# axiom_beta_sensor_cmv12000_tht_v0_16_r1_.net
KiCad netlist of a schematic drawn in EAGLE
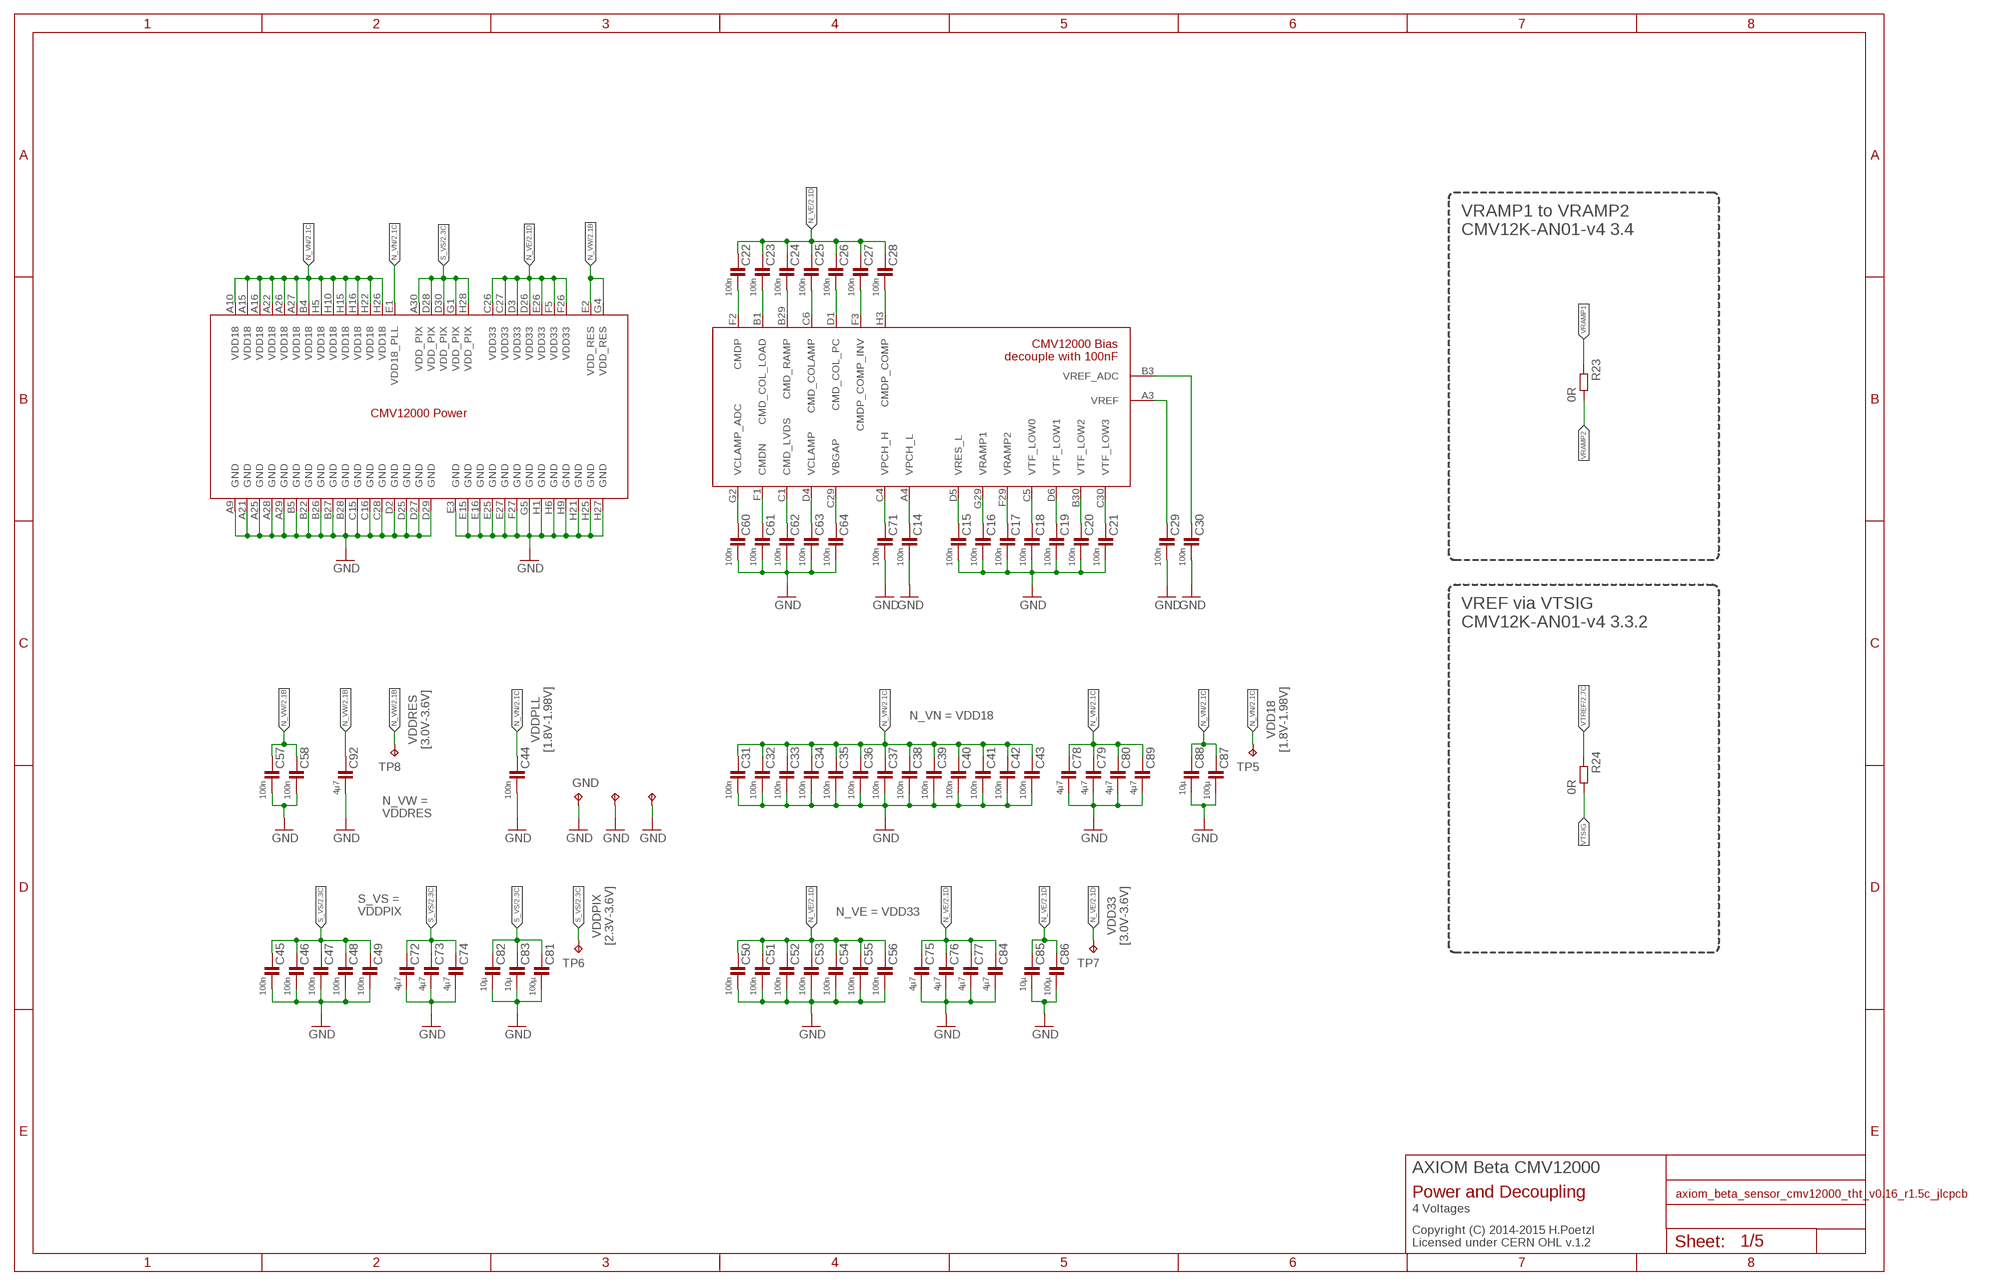
[diagram p0: schematic, sheet 1]
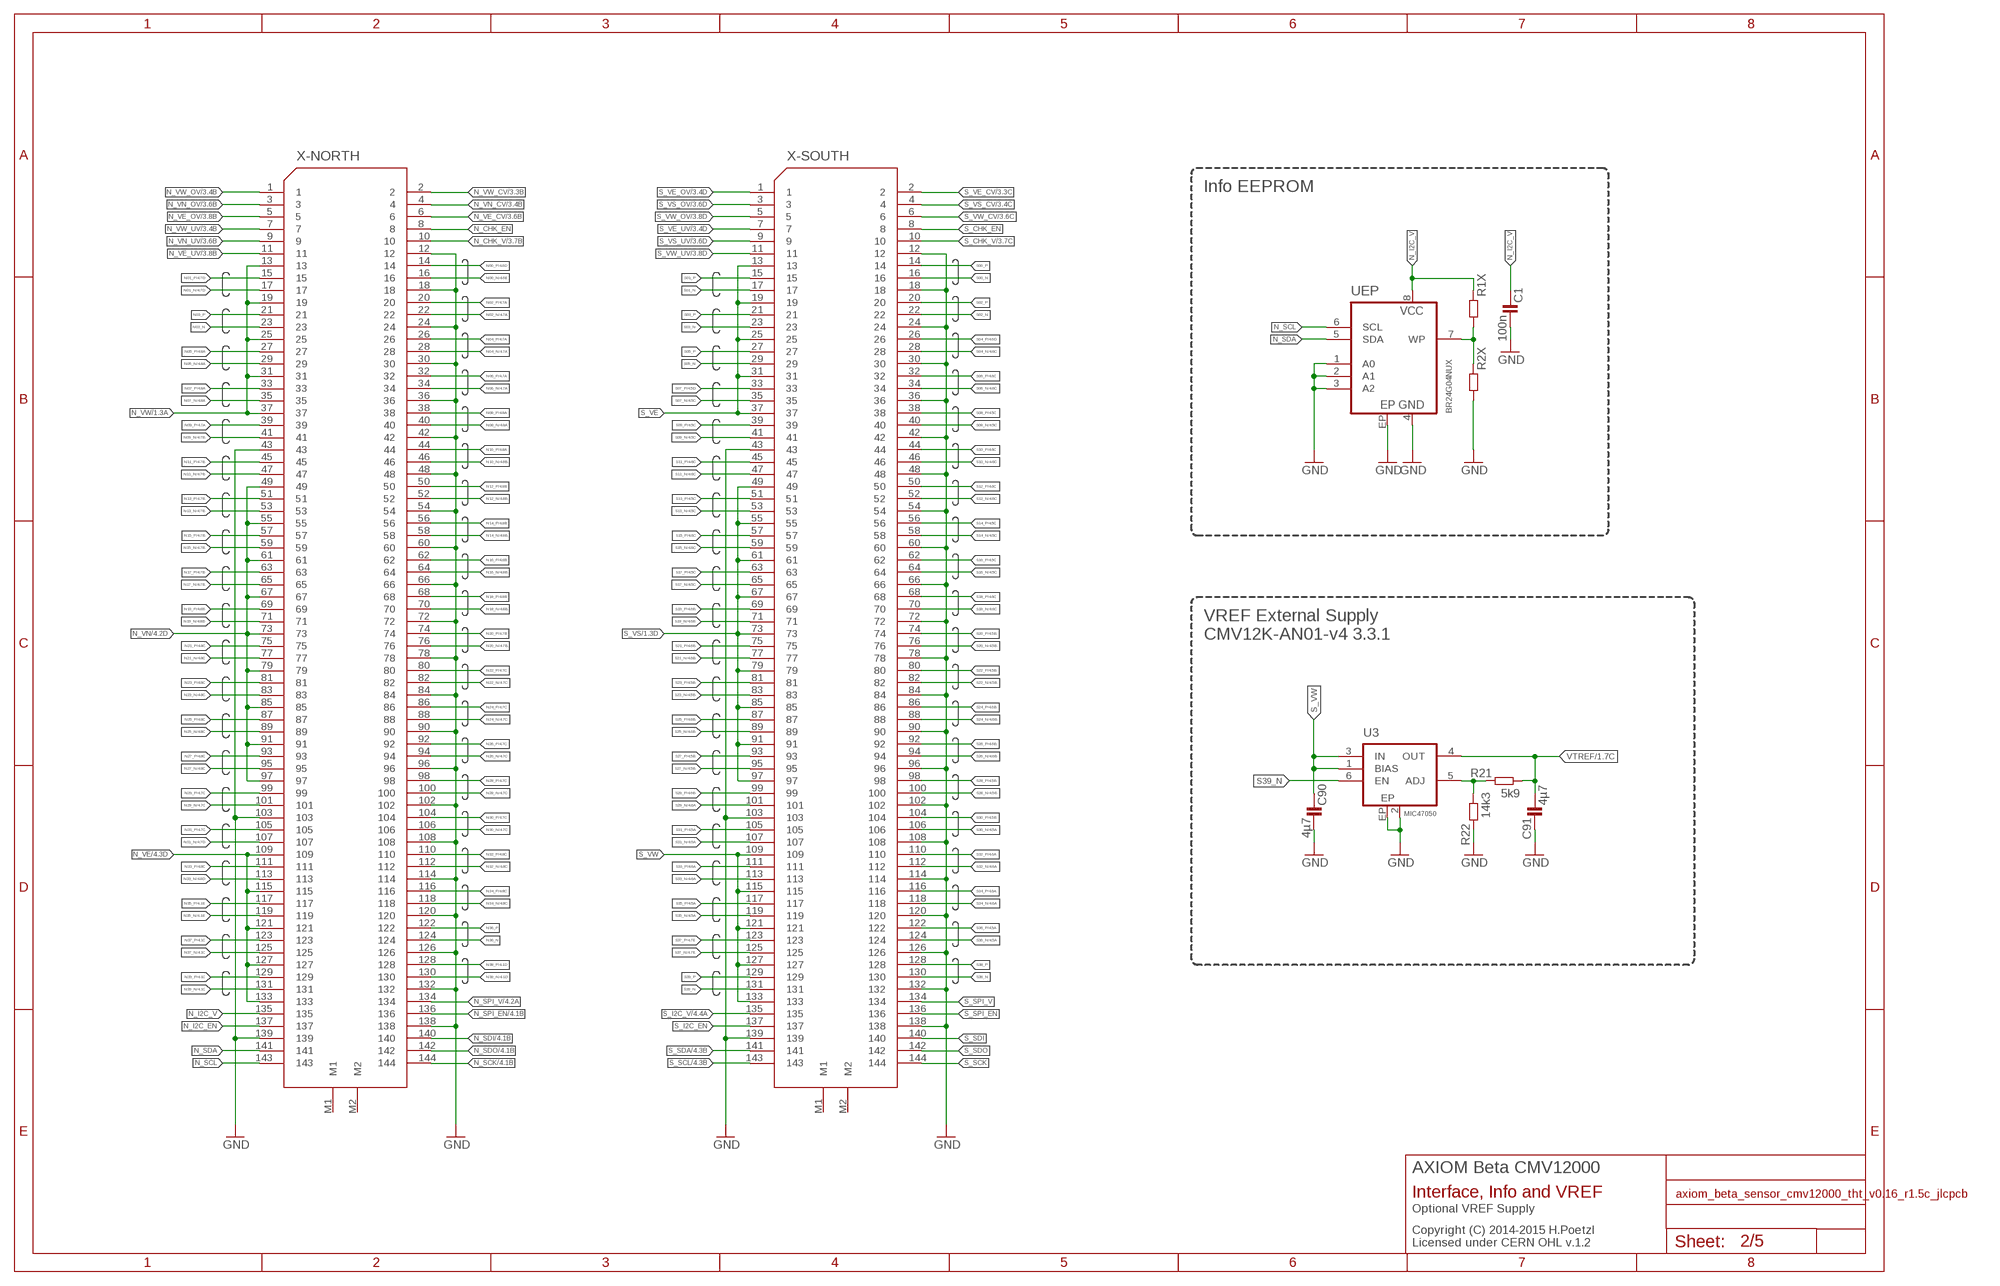
[diagram p1: schematic, sheet 2]
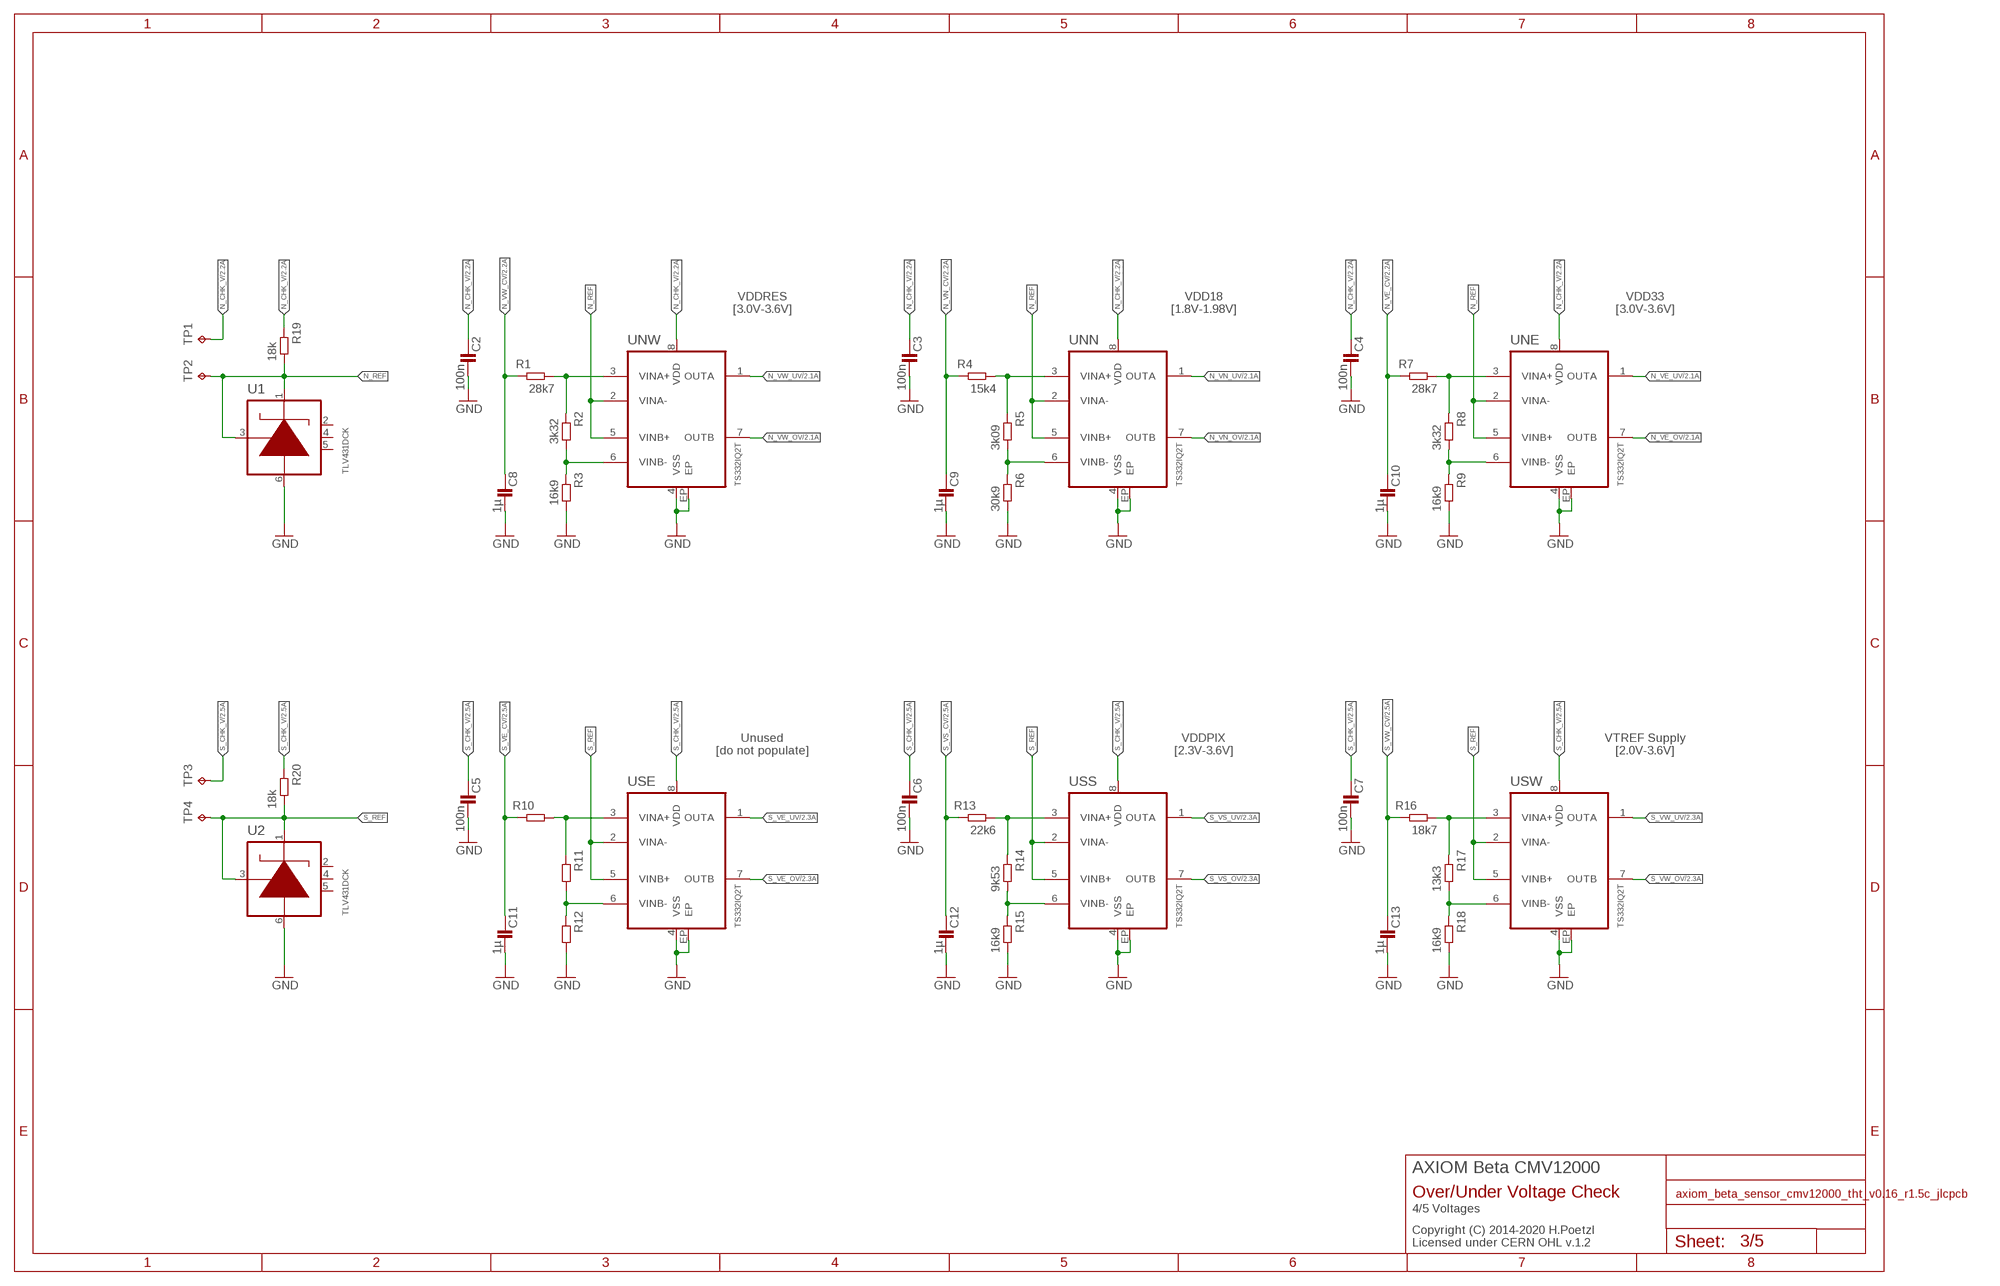
[diagram p2: schematic, sheet 3]
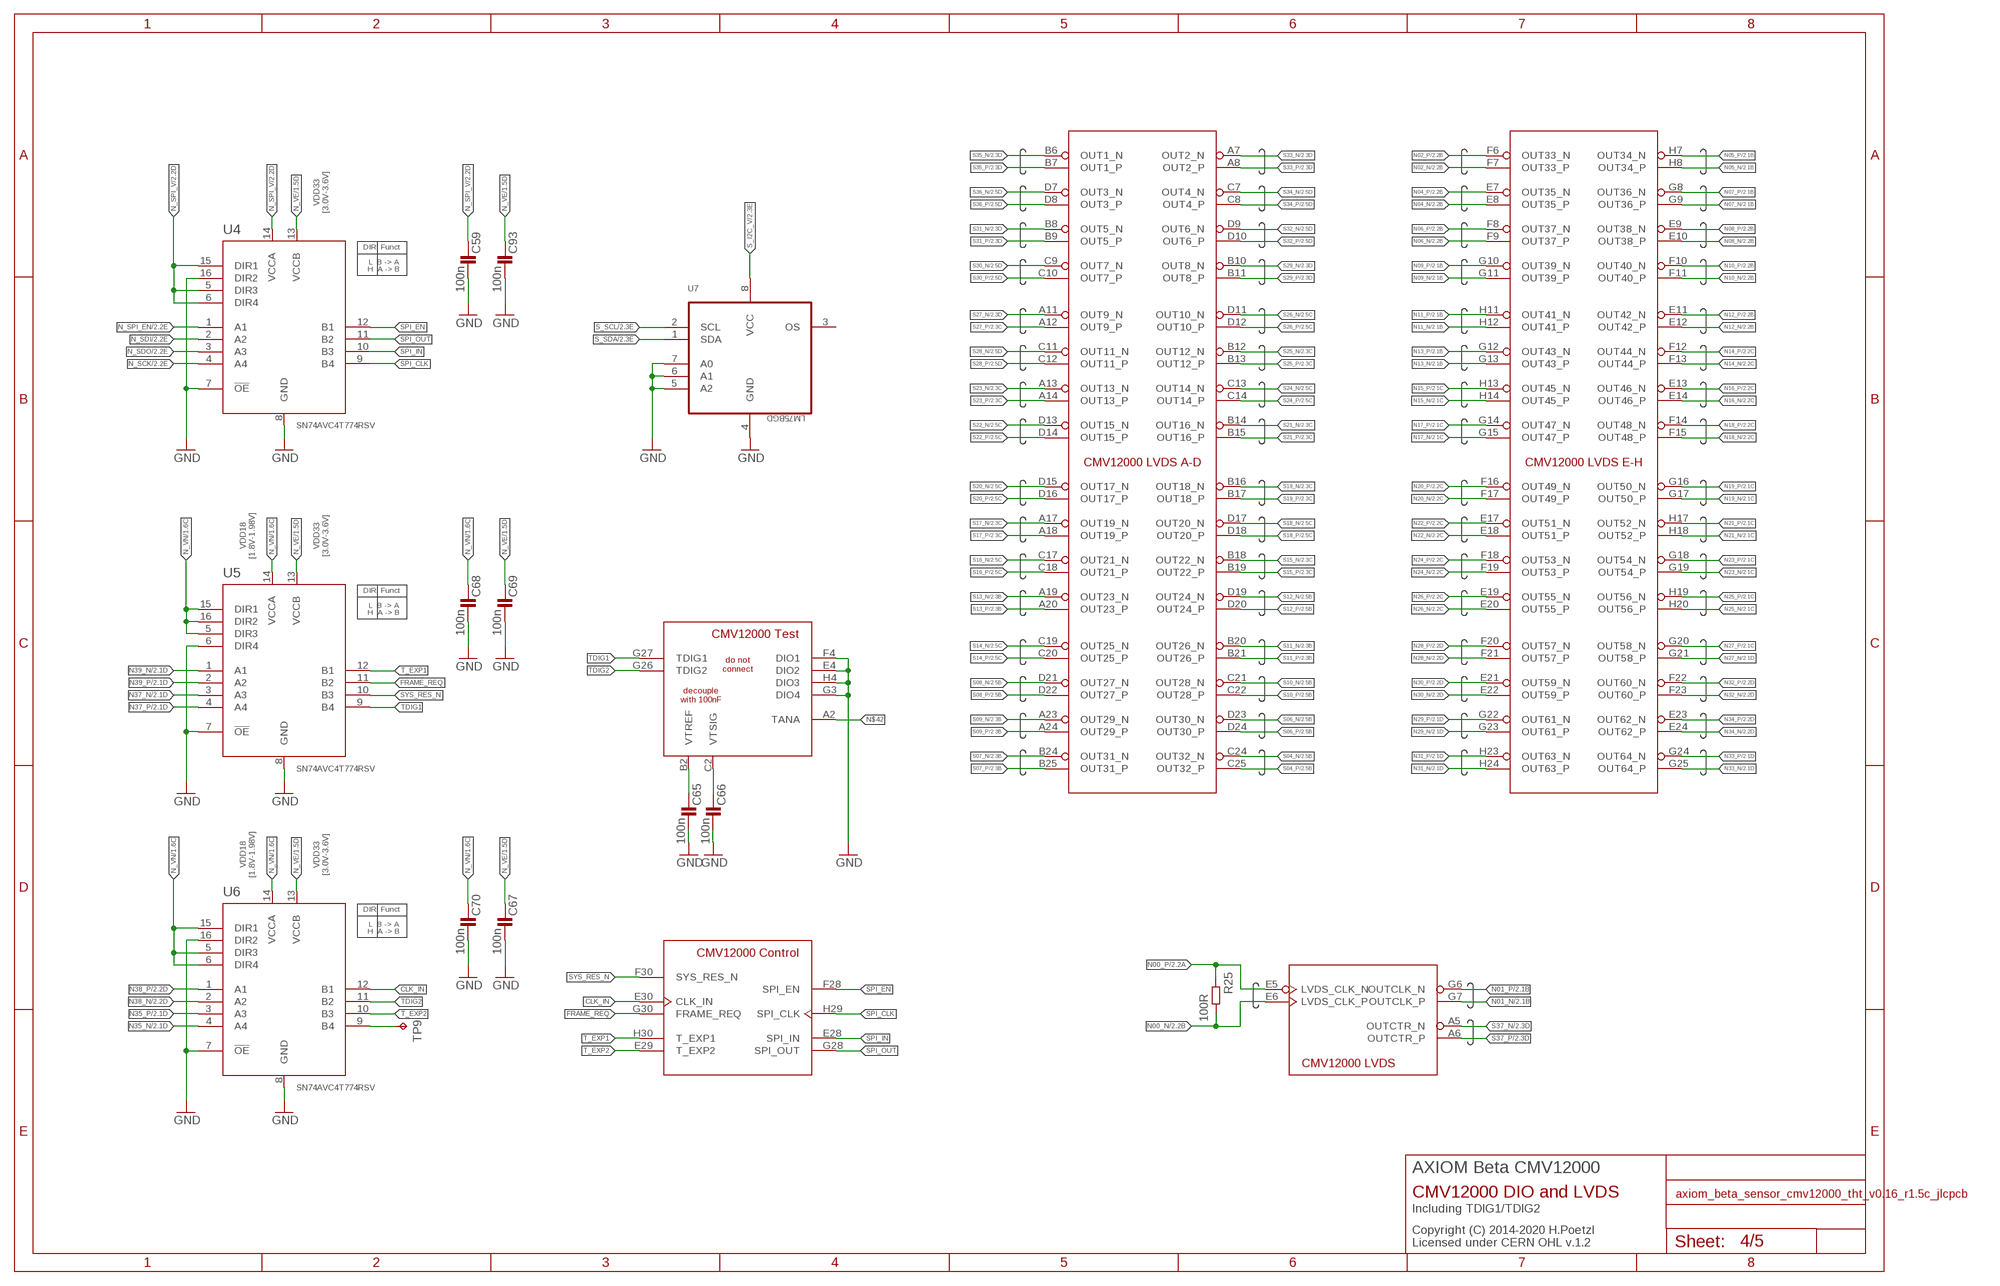
[diagram p3: schematic, sheet 4]
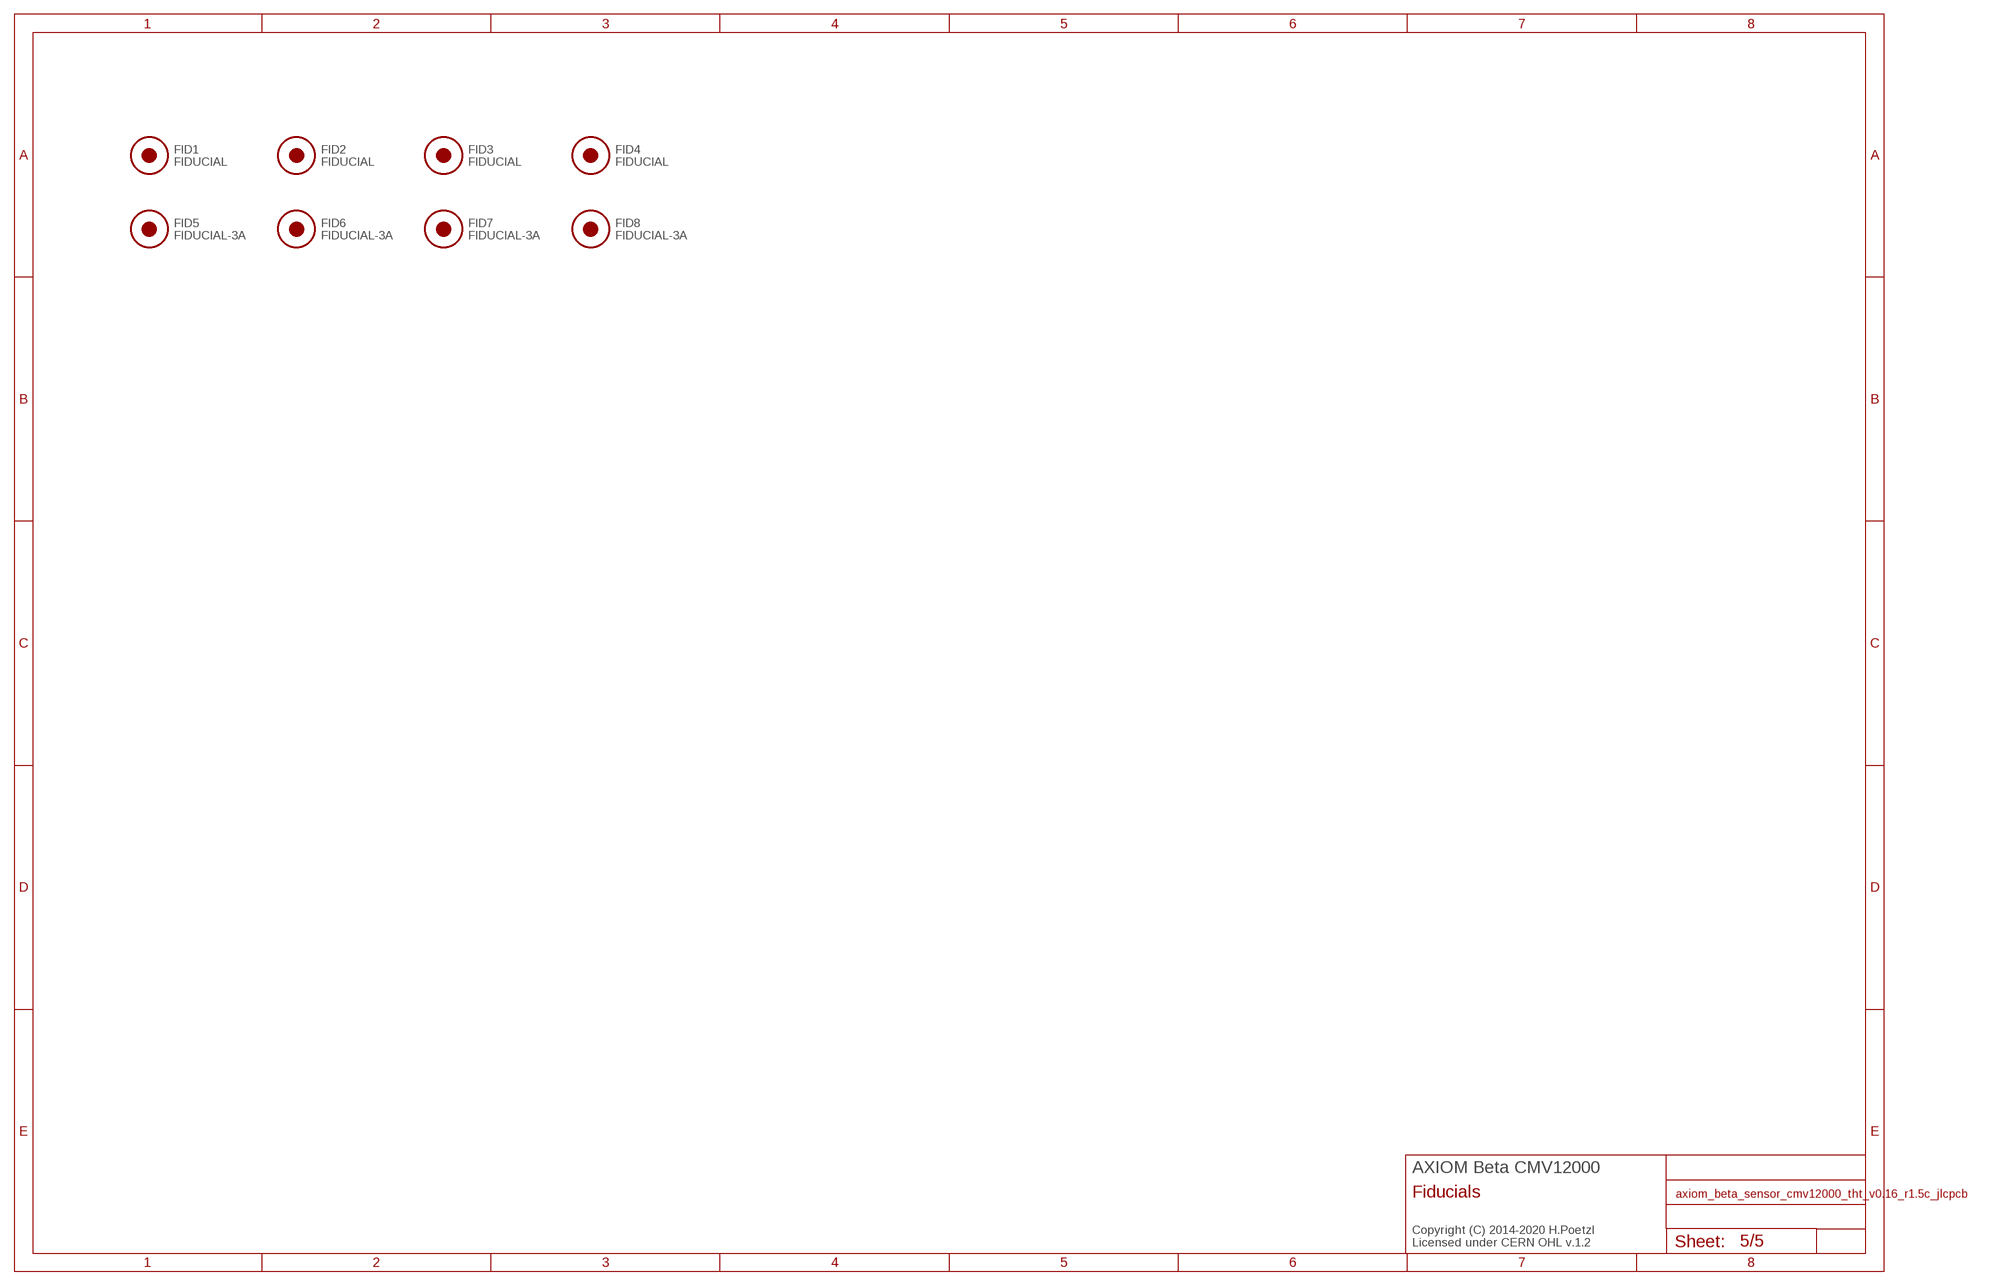
[diagram p4: schematic, sheet 5]

(export (version "E")
  (design (tool "Eeschema 10.0.6"))
  (components
    (comp (ref "C1")
      (value "100n")
      (footprint "eagle-import:0402-C")
      (libsource (lib "eagle-import") (part "C0402-C"))
    )
    (comp (ref "C90")
      (value "4µ7")
      (footprint "eagle-import:0402-C")
      (libsource (lib "eagle-import") (part "C0402-C"))
    )
    (comp (ref "C91")
      (value "4µ7")
      (footprint "eagle-import:0402-C")
      (libsource (lib "eagle-import") (part "C0402-C"))
    )
    (comp (ref "R1X")
      (value "R0402-C")
      (footprint "eagle-import:0402-C")
      (libsource (lib "eagle-import") (part "R0402-C"))
    )
    (comp (ref "R2X")
      (value "R0402-C")
      (footprint "eagle-import:0402-C")
      (libsource (lib "eagle-import") (part "R0402-C"))
    )
    (comp (ref "R21")
      (value "5k9")
      (footprint "eagle-import:0402-C")
      (libsource (lib "eagle-import") (part "R0402-C"))
    )
    (comp (ref "R22")
      (value "14k3")
      (footprint "eagle-import:0402-C")
      (libsource (lib "eagle-import") (part "R0402-C"))
    )
    (comp (ref "U3")
      (value "MIC47050")
      (footprint "eagle-import:MLF-6")
      (libsource (lib "eagle-import") (part "MIC47050-ADJ"))
    )
    (comp (ref "UEP")
      (value "BR24G04NUX")
      (footprint "eagle-import:DFN200X300X100-9N")
      (libsource (lib "eagle-import") (part "BR24G04NUX"))
    )
    (comp (ref "X-NORTH")
      (value "FX10-144P")
      (footprint "eagle-import:FX10A-144P")
      (libsource (lib "eagle-import") (part "FX10-144P"))
    )
    (comp (ref "X-SOUTH")
      (value "FX10-144P")
      (footprint "eagle-import:FX10A-144P")
      (libsource (lib "eagle-import") (part "FX10-144P"))
    )
    (comp (ref "FID1")
      (value "FIDUCIAL")
      (footprint "eagle-import:FID_ARROW")
      (libsource (lib "eagle-import") (part "FIDUCIAL"))
    )
    (comp (ref "FID2")
      (value "FIDUCIAL")
      (footprint "eagle-import:FID_ARROW")
      (libsource (lib "eagle-import") (part "FIDUCIAL"))
    )
    (comp (ref "FID3")
      (value "FIDUCIAL")
      (footprint "eagle-import:FID_ARROW")
      (libsource (lib "eagle-import") (part "FIDUCIAL"))
    )
    (comp (ref "FID4")
      (value "FIDUCIAL")
      (footprint "eagle-import:FID_ARROW")
      (libsource (lib "eagle-import") (part "FIDUCIAL"))
    )
    (comp (ref "FID5")
      (value "FIDUCIAL-3A")
      (footprint "eagle-import:FID_3ARROW")
      (libsource (lib "eagle-import") (part "FIDUCIAL-3A"))
    )
    (comp (ref "FID6")
      (value "FIDUCIAL-3A")
      (footprint "eagle-import:FID_3ARROW")
      (libsource (lib "eagle-import") (part "FIDUCIAL-3A"))
    )
    (comp (ref "FID7")
      (value "FIDUCIAL-3A")
      (footprint "eagle-import:FID_3ARROW")
      (libsource (lib "eagle-import") (part "FIDUCIAL-3A"))
    )
    (comp (ref "FID8")
      (value "FIDUCIAL-3A")
      (footprint "eagle-import:FID_3ARROW")
      (libsource (lib "eagle-import") (part "FIDUCIAL-3A"))
    )
    (comp (ref "C59")
      (value "100n")
      (footprint "eagle-import:0402-C")
      (libsource (lib "eagle-import") (part "C0402-C"))
    )
    (comp (ref "C65")
      (value "100n")
      (footprint "eagle-import:0402-C")
      (libsource (lib "eagle-import") (part "C0402-C"))
    )
    (comp (ref "C66")
      (value "100n")
      (footprint "eagle-import:0402-C")
      (libsource (lib "eagle-import") (part "C0402-C"))
    )
    (comp (ref "C67")
      (value "100n")
      (footprint "eagle-import:0402-C")
      (libsource (lib "eagle-import") (part "C0402-C"))
    )
    (comp (ref "C68")
      (value "100n")
      (footprint "eagle-import:0402-C")
      (libsource (lib "eagle-import") (part "C0402-C"))
    )
    (comp (ref "C69")
      (value "100n")
      (footprint "eagle-import:0402-C")
      (libsource (lib "eagle-import") (part "C0402-C"))
    )
    (comp (ref "C70")
      (value "100n")
      (footprint "eagle-import:0402-C")
      (libsource (lib "eagle-import") (part "C0402-C"))
    )
    (comp (ref "C93")
      (value "100n")
      (footprint "eagle-import:0402-C")
      (libsource (lib "eagle-import") (part "C0402-C"))
    )
    (comp (ref "R25")
      (value "100R")
      (footprint "eagle-import:0402-C")
      (libsource (lib "eagle-import") (part "R0402-C"))
    )
    (comp (ref "SENSOR")
      (value "CMV12000JLCPCB")
      (footprint "eagle-import:10-30-07-237-400T4-JLCPCB")
      (libsource (lib "eagle-import") (part "CMV12000JLCPCB"))
    )
    (comp (ref "TP9")
      (value "TPTP10R")
      (footprint "eagle-import:TP10R")
      (libsource (lib "eagle-import") (part "TPTP10R"))
    )
    (comp (ref "U4")
      (value "SN74AVC4T774RSV")
      (footprint "eagle-import:QFN40P185X265X55-16N")
      (libsource (lib "eagle-import") (part "SN74AVC4T774RSV"))
    )
    (comp (ref "U5")
      (value "SN74AVC4T774RSV")
      (footprint "eagle-import:QFN40P185X265X55-16N")
      (libsource (lib "eagle-import") (part "SN74AVC4T774RSV"))
    )
    (comp (ref "U6")
      (value "SN74AVC4T774RSV")
      (footprint "eagle-import:QFN40P185X265X55-16N")
      (libsource (lib "eagle-import") (part "SN74AVC4T774RSV"))
    )
    (comp (ref "U7")
      (value "LM75BGD")
      (footprint "eagle-import:SOT996-2_3")
      (libsource (lib "eagle-import") (part "LM75BGD"))
    )
    (comp (ref "C2")
      (value "100n")
      (footprint "eagle-import:0402-C")
      (libsource (lib "eagle-import") (part "C0402-C"))
    )
    (comp (ref "C3")
      (value "100n")
      (footprint "eagle-import:0402-C")
      (libsource (lib "eagle-import") (part "C0402-C"))
    )
    (comp (ref "C4")
      (value "100n")
      (footprint "eagle-import:0402-C")
      (libsource (lib "eagle-import") (part "C0402-C"))
    )
    (comp (ref "C5")
      (value "100n")
      (footprint "eagle-import:0402-C")
      (libsource (lib "eagle-import") (part "C0402-C"))
    )
    (comp (ref "C6")
      (value "100n")
      (footprint "eagle-import:0402-C")
      (libsource (lib "eagle-import") (part "C0402-C"))
    )
    (comp (ref "C7")
      (value "100n")
      (footprint "eagle-import:0402-C")
      (libsource (lib "eagle-import") (part "C0402-C"))
    )
    (comp (ref "C8")
      (value "1µ")
      (footprint "eagle-import:0402-C")
      (libsource (lib "eagle-import") (part "C0402-C"))
    )
    (comp (ref "C9")
      (value "1µ")
      (footprint "eagle-import:0402-C")
      (libsource (lib "eagle-import") (part "C0402-C"))
    )
    (comp (ref "C10")
      (value "1µ")
      (footprint "eagle-import:0402-C")
      (libsource (lib "eagle-import") (part "C0402-C"))
    )
    (comp (ref "C11")
      (value "1µ")
      (footprint "eagle-import:0402-C")
      (libsource (lib "eagle-import") (part "C0402-C"))
    )
    (comp (ref "C12")
      (value "1µ")
      (footprint "eagle-import:0402-C")
      (libsource (lib "eagle-import") (part "C0402-C"))
    )
    (comp (ref "C13")
      (value "1µ")
      (footprint "eagle-import:0402-C")
      (libsource (lib "eagle-import") (part "C0402-C"))
    )
    (comp (ref "R1")
      (value "28k7")
      (footprint "eagle-import:0402-C")
      (libsource (lib "eagle-import") (part "R0402-C"))
    )
    (comp (ref "R2")
      (value "3k32")
      (footprint "eagle-import:0402-C")
      (libsource (lib "eagle-import") (part "R0402-C"))
    )
    (comp (ref "R3")
      (value "16k9")
      (footprint "eagle-import:0402-C")
      (libsource (lib "eagle-import") (part "R0402-C"))
    )
    (comp (ref "R4")
      (value "15k4")
      (footprint "eagle-import:0402-C")
      (libsource (lib "eagle-import") (part "R0402-C"))
    )
    (comp (ref "R5")
      (value "3k09")
      (footprint "eagle-import:0402-C")
      (libsource (lib "eagle-import") (part "R0402-C"))
    )
    (comp (ref "R6")
      (value "30k9")
      (footprint "eagle-import:0402-C")
      (libsource (lib "eagle-import") (part "R0402-C"))
    )
    (comp (ref "R7")
      (value "28k7")
      (footprint "eagle-import:0402-C")
      (libsource (lib "eagle-import") (part "R0402-C"))
    )
    (comp (ref "R8")
      (value "3k32")
      (footprint "eagle-import:0402-C")
      (libsource (lib "eagle-import") (part "R0402-C"))
    )
    (comp (ref "R9")
      (value "16k9")
      (footprint "eagle-import:0402-C")
      (libsource (lib "eagle-import") (part "R0402-C"))
    )
    (comp (ref "R10")
      (value "R0402-C")
      (footprint "eagle-import:0402-C")
      (libsource (lib "eagle-import") (part "R0402-C"))
    )
    (comp (ref "R11")
      (value "R0402-C")
      (footprint "eagle-import:0402-C")
      (libsource (lib "eagle-import") (part "R0402-C"))
    )
    (comp (ref "R12")
      (value "R0402-C")
      (footprint "eagle-import:0402-C")
      (libsource (lib "eagle-import") (part "R0402-C"))
    )
    (comp (ref "R13")
      (value "22k6")
      (footprint "eagle-import:0402-C")
      (libsource (lib "eagle-import") (part "R0402-C"))
    )
    (comp (ref "R14")
      (value "9k53")
      (footprint "eagle-import:0402-C")
      (libsource (lib "eagle-import") (part "R0402-C"))
    )
    (comp (ref "R15")
      (value "16k9")
      (footprint "eagle-import:0402-C")
      (libsource (lib "eagle-import") (part "R0402-C"))
    )
    (comp (ref "R16")
      (value "18k7")
      (footprint "eagle-import:0402-C")
      (libsource (lib "eagle-import") (part "R0402-C"))
    )
    (comp (ref "R17")
      (value "13k3")
      (footprint "eagle-import:0402-C")
      (libsource (lib "eagle-import") (part "R0402-C"))
    )
    (comp (ref "R18")
      (value "16k9")
      (footprint "eagle-import:0402-C")
      (libsource (lib "eagle-import") (part "R0402-C"))
    )
    (comp (ref "R19")
      (value "18k")
      (footprint "eagle-import:0402-C")
      (libsource (lib "eagle-import") (part "R0402-C"))
    )
    (comp (ref "R20")
      (value "18k")
      (footprint "eagle-import:0402-C")
      (libsource (lib "eagle-import") (part "R0402-C"))
    )
    (comp (ref "TP1")
      (value "TPTP10R")
      (footprint "eagle-import:TP10R")
      (libsource (lib "eagle-import") (part "TPTP10R"))
    )
    (comp (ref "TP2")
      (value "TPTP10R")
      (footprint "eagle-import:TP10R")
      (libsource (lib "eagle-import") (part "TPTP10R"))
    )
    (comp (ref "TP3")
      (value "TPTP10R")
      (footprint "eagle-import:TP10R")
      (libsource (lib "eagle-import") (part "TPTP10R"))
    )
    (comp (ref "TP4")
      (value "TPTP10R")
      (footprint "eagle-import:TP10R")
      (libsource (lib "eagle-import") (part "TPTP10R"))
    )
    (comp (ref "U1")
      (value "TLV431DCK")
      (footprint "eagle-import:SOT65P210X110-6N")
      (libsource (lib "eagle-import") (part "TLV431DCK"))
    )
    (comp (ref "U2")
      (value "TLV431DCK")
      (footprint "eagle-import:SOT65P210X110-6N")
      (libsource (lib "eagle-import") (part "TLV431DCK"))
    )
    (comp (ref "UNE")
      (value "TS332IQ2T")
      (footprint "eagle-import:DFN200X200X100-9N")
      (libsource (lib "eagle-import") (part "TS332IQ2T"))
    )
    (comp (ref "UNN")
      (value "TS332IQ2T")
      (footprint "eagle-import:DFN200X200X100-9N")
      (libsource (lib "eagle-import") (part "TS332IQ2T"))
    )
    (comp (ref "UNW")
      (value "TS332IQ2T")
      (footprint "eagle-import:DFN200X200X100-9N")
      (libsource (lib "eagle-import") (part "TS332IQ2T"))
    )
    (comp (ref "USE")
      (value "TS332IQ2T")
      (footprint "eagle-import:DFN200X200X100-9N")
      (libsource (lib "eagle-import") (part "TS332IQ2T"))
    )
    (comp (ref "USS")
      (value "TS332IQ2T")
      (footprint "eagle-import:DFN200X200X100-9N")
      (libsource (lib "eagle-import") (part "TS332IQ2T"))
    )
    (comp (ref "USW")
      (value "TS332IQ2T")
      (footprint "eagle-import:DFN200X200X100-9N")
      (libsource (lib "eagle-import") (part "TS332IQ2T"))
    )
    (comp (ref "C14")
      (value "100n")
      (footprint "eagle-import:0402-C")
      (libsource (lib "eagle-import") (part "C0402-C"))
    )
    (comp (ref "C15")
      (value "100n")
      (footprint "eagle-import:0402-C")
      (libsource (lib "eagle-import") (part "C0402-C"))
    )
    (comp (ref "C16")
      (value "100n")
      (footprint "eagle-import:0402-C")
      (libsource (lib "eagle-import") (part "C0402-C"))
    )
    (comp (ref "C17")
      (value "100n")
      (footprint "eagle-import:0402-C")
      (libsource (lib "eagle-import") (part "C0402-C"))
    )
    (comp (ref "C18")
      (value "100n")
      (footprint "eagle-import:0402-C")
      (libsource (lib "eagle-import") (part "C0402-C"))
    )
    (comp (ref "C19")
      (value "100n")
      (footprint "eagle-import:0402-C")
      (libsource (lib "eagle-import") (part "C0402-C"))
    )
    (comp (ref "C20")
      (value "100n")
      (footprint "eagle-import:0402-C")
      (libsource (lib "eagle-import") (part "C0402-C"))
    )
    (comp (ref "C21")
      (value "100n")
      (footprint "eagle-import:0402-C")
      (libsource (lib "eagle-import") (part "C0402-C"))
    )
    (comp (ref "C22")
      (value "100n")
      (footprint "eagle-import:0402-C")
      (libsource (lib "eagle-import") (part "C0402-C"))
    )
    (comp (ref "C23")
      (value "100n")
      (footprint "eagle-import:0402-C")
      (libsource (lib "eagle-import") (part "C0402-C"))
    )
    (comp (ref "C24")
      (value "100n")
      (footprint "eagle-import:0402-C")
      (libsource (lib "eagle-import") (part "C0402-C"))
    )
    (comp (ref "C25")
      (value "100n")
      (footprint "eagle-import:0402-C")
      (libsource (lib "eagle-import") (part "C0402-C"))
    )
    (comp (ref "C26")
      (value "100n")
      (footprint "eagle-import:0402-C")
      (libsource (lib "eagle-import") (part "C0402-C"))
    )
    (comp (ref "C27")
      (value "100n")
      (footprint "eagle-import:0402-C")
      (libsource (lib "eagle-import") (part "C0402-C"))
    )
    (comp (ref "C28")
      (value "100n")
      (footprint "eagle-import:0402-C")
      (libsource (lib "eagle-import") (part "C0402-C"))
    )
    (comp (ref "C29")
      (value "100n")
      (footprint "eagle-import:0402-C")
      (libsource (lib "eagle-import") (part "C0402-C"))
    )
    (comp (ref "C30")
      (value "100n")
      (footprint "eagle-import:0402-C")
      (libsource (lib "eagle-import") (part "C0402-C"))
    )
    (comp (ref "C31")
      (value "100n")
      (footprint "eagle-import:0402-C")
      (libsource (lib "eagle-import") (part "C0402-C"))
    )
    (comp (ref "C32")
      (value "100n")
      (footprint "eagle-import:0402-C")
      (libsource (lib "eagle-import") (part "C0402-C"))
    )
    (comp (ref "C33")
      (value "100n")
      (footprint "eagle-import:0402-C")
      (libsource (lib "eagle-import") (part "C0402-C"))
    )
    (comp (ref "C34")
      (value "100n")
      (footprint "eagle-import:0402-C")
      (libsource (lib "eagle-import") (part "C0402-C"))
    )
    (comp (ref "C35")
      (value "100n")
      (footprint "eagle-import:0402-C")
      (libsource (lib "eagle-import") (part "C0402-C"))
    )
    (comp (ref "C36")
      (value "100n")
      (footprint "eagle-import:0402-C")
      (libsource (lib "eagle-import") (part "C0402-C"))
    )
    (comp (ref "C37")
      (value "100n")
      (footprint "eagle-import:0402-C")
      (libsource (lib "eagle-import") (part "C0402-C"))
    )
    (comp (ref "C38")
      (value "100n")
      (footprint "eagle-import:0402-C")
      (libsource (lib "eagle-import") (part "C0402-C"))
    )
    (comp (ref "C39")
      (value "100n")
      (footprint "eagle-import:0402-C")
      (libsource (lib "eagle-import") (part "C0402-C"))
    )
    (comp (ref "C40")
      (value "100n")
      (footprint "eagle-import:0402-C")
      (libsource (lib "eagle-import") (part "C0402-C"))
    )
    (comp (ref "C41")
      (value "100n")
      (footprint "eagle-import:0402-C")
      (libsource (lib "eagle-import") (part "C0402-C"))
    )
    (comp (ref "C42")
      (value "100n")
      (footprint "eagle-import:0402-C")
      (libsource (lib "eagle-import") (part "C0402-C"))
    )
    (comp (ref "C43")
      (value "100n")
      (footprint "eagle-import:0402-C")
      (libsource (lib "eagle-import") (part "C0402-C"))
    )
    (comp (ref "C44")
      (value "100n")
      (footprint "eagle-import:0402-C")
      (libsource (lib "eagle-import") (part "C0402-C"))
    )
    (comp (ref "C45")
      (value "100n")
      (footprint "eagle-import:0402-C")
      (libsource (lib "eagle-import") (part "C0402-C"))
    )
    (comp (ref "C46")
      (value "100n")
      (footprint "eagle-import:0402-C")
      (libsource (lib "eagle-import") (part "C0402-C"))
    )
    (comp (ref "C47")
      (value "100n")
      (footprint "eagle-import:0402-C")
      (libsource (lib "eagle-import") (part "C0402-C"))
    )
    (comp (ref "C48")
      (value "100n")
      (footprint "eagle-import:0402-C")
      (libsource (lib "eagle-import") (part "C0402-C"))
    )
    (comp (ref "C49")
      (value "100n")
      (footprint "eagle-import:0402-C")
      (libsource (lib "eagle-import") (part "C0402-C"))
    )
    (comp (ref "C50")
      (value "100n")
      (footprint "eagle-import:0402-C")
      (libsource (lib "eagle-import") (part "C0402-C"))
    )
    (comp (ref "C51")
      (value "100n")
      (footprint "eagle-import:0402-C")
      (libsource (lib "eagle-import") (part "C0402-C"))
    )
    (comp (ref "C52")
      (value "100n")
      (footprint "eagle-import:0402-C")
      (libsource (lib "eagle-import") (part "C0402-C"))
    )
    (comp (ref "C53")
      (value "100n")
      (footprint "eagle-import:0402-C")
      (libsource (lib "eagle-import") (part "C0402-C"))
    )
    (comp (ref "C54")
      (value "100n")
      (footprint "eagle-import:0402-C")
      (libsource (lib "eagle-import") (part "C0402-C"))
    )
    (comp (ref "C55")
      (value "100n")
      (footprint "eagle-import:0402-C")
      (libsource (lib "eagle-import") (part "C0402-C"))
    )
    (comp (ref "C56")
      (value "100n")
      (footprint "eagle-import:0402-C")
      (libsource (lib "eagle-import") (part "C0402-C"))
    )
    (comp (ref "C57")
      (value "100n")
      (footprint "eagle-import:0402-C")
      (libsource (lib "eagle-import") (part "C0402-C"))
    )
    (comp (ref "C58")
      (value "100n")
      (footprint "eagle-import:0402-C")
      (libsource (lib "eagle-import") (part "C0402-C"))
    )
    (comp (ref "C60")
      (value "100n")
      (footprint "eagle-import:0402-C")
      (libsource (lib "eagle-import") (part "C0402-C"))
    )
    (comp (ref "C61")
      (value "100n")
      (footprint "eagle-import:0402-C")
      (libsource (lib "eagle-import") (part "C0402-C"))
    )
    (comp (ref "C62")
      (value "100n")
      (footprint "eagle-import:0402-C")
      (libsource (lib "eagle-import") (part "C0402-C"))
    )
    (comp (ref "C63")
      (value "100n")
      (footprint "eagle-import:0402-C")
      (libsource (lib "eagle-import") (part "C0402-C"))
    )
    (comp (ref "C64")
      (value "100n")
      (footprint "eagle-import:0402-C")
      (libsource (lib "eagle-import") (part "C0402-C"))
    )
    (comp (ref "C71")
      (value "100n")
      (footprint "eagle-import:0402-C")
      (libsource (lib "eagle-import") (part "C0402-C"))
    )
    (comp (ref "C72")
      (value "4µ7")
      (footprint "eagle-import:0402-B")
      (libsource (lib "eagle-import") (part "C0402-B"))
    )
    (comp (ref "C73")
      (value "4µ7")
      (footprint "eagle-import:0402-C")
      (libsource (lib "eagle-import") (part "C0402-C"))
    )
    (comp (ref "C74")
      (value "4µ7")
      (footprint "eagle-import:0402-C")
      (libsource (lib "eagle-import") (part "C0402-C"))
    )
    (comp (ref "C75")
      (value "4µ7")
      (footprint "eagle-import:0402-C")
      (libsource (lib "eagle-import") (part "C0402-C"))
    )
    (comp (ref "C76")
      (value "4µ7")
      (footprint "eagle-import:0402-C")
      (libsource (lib "eagle-import") (part "C0402-C"))
    )
    (comp (ref "C77")
      (value "4µ7")
      (footprint "eagle-import:0402-B")
      (libsource (lib "eagle-import") (part "C0402-B"))
    )
    (comp (ref "C78")
      (value "4µ7")
      (footprint "eagle-import:0402-B")
      (libsource (lib "eagle-import") (part "C0402-B"))
    )
    (comp (ref "C79")
      (value "4µ7")
      (footprint "eagle-import:0402-C")
      (libsource (lib "eagle-import") (part "C0402-C"))
    )
    (comp (ref "C80")
      (value "4µ7")
      (footprint "eagle-import:0402-C")
      (libsource (lib "eagle-import") (part "C0402-C"))
    )
    (comp (ref "C81")
      (value "100µ")
      (footprint "eagle-import:1206-B")
      (libsource (lib "eagle-import") (part "C1206-B"))
    )
    (comp (ref "C82")
      (value "10µ")
      (footprint "eagle-import:0603-C")
      (libsource (lib "eagle-import") (part "C0603-C"))
    )
    (comp (ref "C83")
      (value "10µ")
      (footprint "eagle-import:0603-C")
      (libsource (lib "eagle-import") (part "C0603-C"))
    )
    (comp (ref "C84")
      (value "4µ7")
      (footprint "eagle-import:0402-C")
      (libsource (lib "eagle-import") (part "C0402-C"))
    )
    (comp (ref "C85")
      (value "10µ")
      (footprint "eagle-import:0603-C")
      (libsource (lib "eagle-import") (part "C0603-C"))
    )
    (comp (ref "C86")
      (value "100µ")
      (footprint "eagle-import:1206-B")
      (libsource (lib "eagle-import") (part "C1206-B"))
    )
    (comp (ref "C87")
      (value "100µ")
      (footprint "eagle-import:1206-B")
      (libsource (lib "eagle-import") (part "C1206-B"))
    )
    (comp (ref "C88")
      (value "10µ")
      (footprint "eagle-import:0603-C")
      (libsource (lib "eagle-import") (part "C0603-C"))
    )
    (comp (ref "C89")
      (value "4µ7")
      (footprint "eagle-import:0402-C")
      (libsource (lib "eagle-import") (part "C0402-C"))
    )
    (comp (ref "C92")
      (value "4µ7")
      (footprint "eagle-import:0402-C")
      (libsource (lib "eagle-import") (part "C0402-C"))
    )
    (comp (ref "GND")
      (value "TPTP10R")
      (footprint "eagle-import:TP10R")
      (libsource (lib "eagle-import") (part "TPTP10R"))
    )
    (comp (ref "GND75")
      (value "TPTP10R")
      (footprint "eagle-import:TP10R")
      (libsource (lib "eagle-import") (part "TPTP10R"))
    )
    (comp (ref "GND77")
      (value "TPTP10R")
      (footprint "eagle-import:TP10R")
      (libsource (lib "eagle-import") (part "TPTP10R"))
    )
    (comp (ref "R23")
      (value "0R")
      (footprint "eagle-import:0402-C")
      (libsource (lib "eagle-import") (part "R0402-C"))
    )
    (comp (ref "R24")
      (value "0R")
      (footprint "eagle-import:0402-C")
      (libsource (lib "eagle-import") (part "R0402-C"))
    )
    (comp (ref "TP5")
      (value "TPTP10R")
      (footprint "eagle-import:TP10R")
      (libsource (lib "eagle-import") (part "TPTP10R"))
    )
    (comp (ref "TP6")
      (value "TPTP10R")
      (footprint "eagle-import:TP10R")
      (libsource (lib "eagle-import") (part "TPTP10R"))
    )
    (comp (ref "TP7")
      (value "TPTP10R")
      (footprint "eagle-import:TP10R")
      (libsource (lib "eagle-import") (part "TPTP10R"))
    )
    (comp (ref "TP8")
      (value "TPTP10R")
      (footprint "eagle-import:TP10R")
      (libsource (lib "eagle-import") (part "TPTP10R"))
    )
  )
  (nets
    (net (code "1") (name "CLK_IN") (class "Default")
      (node (ref "SENSOR") (pin "E30") (pinfunction "CLK_IN_E30") (pintype "input"))
      (node (ref "U6") (pin "12") (pinfunction "B1_12") (pintype "bidirectional"))
    )
    (net (code "2") (name "FRAME_REQ") (class "Default")
      (node (ref "SENSOR") (pin "G30") (pinfunction "FRAME_REQ_G30") (pintype "input"))
      (node (ref "U5") (pin "11") (pinfunction "B2_11") (pintype "bidirectional"))
    )
    (net (code "3") (name "GND") (class "Default")
      (node (ref "C1") (pin "2") (pinfunction "2_2") (pintype "passive"))
      (node (ref "C10") (pin "2") (pinfunction "2_2") (pintype "passive"))
      (node (ref "C11") (pin "2") (pinfunction "2_2") (pintype "passive"))
      (node (ref "C12") (pin "2") (pinfunction "2_2") (pintype "passive"))
      (node (ref "C13") (pin "2") (pinfunction "2_2") (pintype "passive"))
      (node (ref "C14") (pin "2") (pinfunction "2_2") (pintype "passive"))
      (node (ref "C15") (pin "2") (pinfunction "2_2") (pintype "passive"))
      (node (ref "C16") (pin "2") (pinfunction "2_2") (pintype "passive"))
      (node (ref "C17") (pin "2") (pinfunction "2_2") (pintype "passive"))
      (node (ref "C18") (pin "2") (pinfunction "2_2") (pintype "passive"))
      (node (ref "C19") (pin "2") (pinfunction "2_2") (pintype "passive"))
      (node (ref "C2") (pin "2") (pinfunction "2_2") (pintype "passive"))
      (node (ref "C20") (pin "2") (pinfunction "2_2") (pintype "passive"))
      (node (ref "C21") (pin "2") (pinfunction "2_2") (pintype "passive"))
      (node (ref "C29") (pin "2") (pinfunction "2_2") (pintype "passive"))
      (node (ref "C3") (pin "2") (pinfunction "2_2") (pintype "passive"))
      (node (ref "C30") (pin "2") (pinfunction "2_2") (pintype "passive"))
      (node (ref "C31") (pin "2") (pinfunction "2_2") (pintype "passive"))
      (node (ref "C32") (pin "2") (pinfunction "2_2") (pintype "passive"))
      (node (ref "C33") (pin "2") (pinfunction "2_2") (pintype "passive"))
      (node (ref "C34") (pin "2") (pinfunction "2_2") (pintype "passive"))
      (node (ref "C35") (pin "2") (pinfunction "2_2") (pintype "passive"))
      (node (ref "C36") (pin "2") (pinfunction "2_2") (pintype "passive"))
      (node (ref "C37") (pin "2") (pinfunction "2_2") (pintype "passive"))
      (node (ref "C38") (pin "2") (pinfunction "2_2") (pintype "passive"))
      (node (ref "C39") (pin "2") (pinfunction "2_2") (pintype "passive"))
      (node (ref "C4") (pin "2") (pinfunction "2_2") (pintype "passive"))
      (node (ref "C40") (pin "2") (pinfunction "2_2") (pintype "passive"))
      (node (ref "C41") (pin "2") (pinfunction "2_2") (pintype "passive"))
      (node (ref "C42") (pin "2") (pinfunction "2_2") (pintype "passive"))
      (node (ref "C43") (pin "2") (pinfunction "2_2") (pintype "passive"))
      (node (ref "C44") (pin "2") (pinfunction "2_2") (pintype "passive"))
      (node (ref "C45") (pin "2") (pinfunction "2_2") (pintype "passive"))
      (node (ref "C46") (pin "2") (pinfunction "2_2") (pintype "passive"))
      (node (ref "C47") (pin "2") (pinfunction "2_2") (pintype "passive"))
      (node (ref "C48") (pin "2") (pinfunction "2_2") (pintype "passive"))
      (node (ref "C49") (pin "2") (pinfunction "2_2") (pintype "passive"))
      (node (ref "C5") (pin "2") (pinfunction "2_2") (pintype "passive"))
      (node (ref "C50") (pin "2") (pinfunction "2_2") (pintype "passive"))
      (node (ref "C51") (pin "2") (pinfunction "2_2") (pintype "passive"))
      (node (ref "C52") (pin "2") (pinfunction "2_2") (pintype "passive"))
      (node (ref "C53") (pin "2") (pinfunction "2_2") (pintype "passive"))
      (node (ref "C54") (pin "2") (pinfunction "2_2") (pintype "passive"))
      (node (ref "C55") (pin "2") (pinfunction "2_2") (pintype "passive"))
      (node (ref "C56") (pin "2") (pinfunction "2_2") (pintype "passive"))
      (node (ref "C57") (pin "2") (pinfunction "2_2") (pintype "passive"))
      (node (ref "C58") (pin "2") (pinfunction "2_2") (pintype "passive"))
      (node (ref "C59") (pin "2") (pinfunction "2_2") (pintype "passive"))
      (node (ref "C6") (pin "2") (pinfunction "2_2") (pintype "passive"))
      (node (ref "C60") (pin "2") (pinfunction "2_2") (pintype "passive"))
      (node (ref "C61") (pin "2") (pinfunction "2_2") (pintype "passive"))
      (node (ref "C62") (pin "2") (pinfunction "2_2") (pintype "passive"))
      (node (ref "C63") (pin "2") (pinfunction "2_2") (pintype "passive"))
      (node (ref "C64") (pin "2") (pinfunction "2_2") (pintype "passive"))
      (node (ref "C65") (pin "2") (pinfunction "2_2") (pintype "passive"))
      (node (ref "C66") (pin "2") (pinfunction "2_2") (pintype "passive"))
      (node (ref "C67") (pin "2") (pinfunction "2_2") (pintype "passive"))
      (node (ref "C68") (pin "2") (pinfunction "2_2") (pintype "passive"))
      (node (ref "C69") (pin "2") (pinfunction "2_2") (pintype "passive"))
      (node (ref "C7") (pin "2") (pinfunction "2_2") (pintype "passive"))
      (node (ref "C70") (pin "2") (pinfunction "2_2") (pintype "passive"))
      (node (ref "C71") (pin "2") (pinfunction "2_2") (pintype "passive"))
      (node (ref "C72") (pin "2") (pinfunction "2_2") (pintype "passive"))
      (node (ref "C73") (pin "2") (pinfunction "2_2") (pintype "passive"))
      (node (ref "C74") (pin "2") (pinfunction "2_2") (pintype "passive"))
      (node (ref "C75") (pin "2") (pinfunction "2_2") (pintype "passive"))
      (node (ref "C76") (pin "2") (pinfunction "2_2") (pintype "passive"))
      (node (ref "C77") (pin "2") (pinfunction "2_2") (pintype "passive"))
      (node (ref "C78") (pin "2") (pinfunction "2_2") (pintype "passive"))
      (node (ref "C79") (pin "2") (pinfunction "2_2") (pintype "passive"))
      (node (ref "C8") (pin "2") (pinfunction "2_2") (pintype "passive"))
      (node (ref "C80") (pin "2") (pinfunction "2_2") (pintype "passive"))
      (node (ref "C81") (pin "2") (pinfunction "2_2") (pintype "passive"))
      (node (ref "C82") (pin "2") (pinfunction "2_2") (pintype "passive"))
      (node (ref "C83") (pin "2") (pinfunction "2_2") (pintype "passive"))
      (node (ref "C84") (pin "2") (pinfunction "2_2") (pintype "passive"))
      (node (ref "C85") (pin "2") (pinfunction "2_2") (pintype "passive"))
      (node (ref "C86") (pin "2") (pinfunction "2_2") (pintype "passive"))
      (node (ref "C87") (pin "2") (pinfunction "2_2") (pintype "passive"))
      (node (ref "C88") (pin "2") (pinfunction "2_2") (pintype "passive"))
      (node (ref "C89") (pin "2") (pinfunction "2_2") (pintype "passive"))
      (node (ref "C9") (pin "2") (pinfunction "2_2") (pintype "passive"))
      (node (ref "C90") (pin "2") (pinfunction "2_2") (pintype "passive"))
      (node (ref "C91") (pin "1") (pinfunction "1_1") (pintype "passive"))
      (node (ref "C92") (pin "2") (pinfunction "2_2") (pintype "passive"))
      (node (ref "C93") (pin "2") (pinfunction "2_2") (pintype "passive"))
      (node (ref "GND") (pin "TP") (pinfunction "TP_TP") (pintype "input"))
      (node (ref "GND75") (pin "TP") (pinfunction "TP_TP") (pintype "input"))
      (node (ref "GND77") (pin "TP") (pinfunction "TP_TP") (pintype "input"))
      (node (ref "R12") (pin "2") (pinfunction "2_2") (pintype "passive"))
      (node (ref "R15") (pin "2") (pinfunction "2_2") (pintype "passive"))
      (node (ref "R18") (pin "2") (pinfunction "2_2") (pintype "passive"))
      (node (ref "R22") (pin "1") (pinfunction "1_1") (pintype "passive"))
      (node (ref "R2X") (pin "2") (pinfunction "2_2") (pintype "passive"))
      (node (ref "R3") (pin "2") (pinfunction "2_2") (pintype "passive"))
      (node (ref "R6") (pin "2") (pinfunction "2_2") (pintype "passive"))
      (node (ref "R9") (pin "2") (pinfunction "2_2") (pintype "passive"))
      (node (ref "SENSOR") (pin "A21") (pinfunction "GND_A21") (pintype "power_in"))
      (node (ref "SENSOR") (pin "A25") (pinfunction "GND_A25") (pintype "power_in"))
      (node (ref "SENSOR") (pin "A28") (pinfunction "GND_A28") (pintype "power_in"))
      (node (ref "SENSOR") (pin "A29") (pinfunction "GND_A29") (pintype "power_in"))
      (node (ref "SENSOR") (pin "A9") (pinfunction "GND_A9") (pintype "power_in"))
      (node (ref "SENSOR") (pin "B22") (pinfunction "GND_B22") (pintype "power_in"))
      (node (ref "SENSOR") (pin "B26") (pinfunction "GND_B26") (pintype "power_in"))
      (node (ref "SENSOR") (pin "B27") (pinfunction "GND_B27") (pintype "power_in"))
      (node (ref "SENSOR") (pin "B28") (pinfunction "GND_B28") (pintype "power_in"))
      (node (ref "SENSOR") (pin "B5") (pinfunction "GND_B5") (pintype "power_in"))
      (node (ref "SENSOR") (pin "C15") (pinfunction "GND_C15") (pintype "power_in"))
      (node (ref "SENSOR") (pin "C16") (pinfunction "GND_C16") (pintype "power_in"))
      (node (ref "SENSOR") (pin "C28") (pinfunction "GND_C28") (pintype "power_in"))
      (node (ref "SENSOR") (pin "D2") (pinfunction "GND_D2") (pintype "power_in"))
      (node (ref "SENSOR") (pin "D25") (pinfunction "GND_D25") (pintype "power_in"))
      (node (ref "SENSOR") (pin "D27") (pinfunction "GND_D27") (pintype "power_in"))
      (node (ref "SENSOR") (pin "D29") (pinfunction "GND_D29") (pintype "power_in"))
      (node (ref "SENSOR") (pin "E15") (pinfunction "GND_E15") (pintype "power_in"))
      (node (ref "SENSOR") (pin "E16") (pinfunction "GND_E16") (pintype "power_in"))
      (node (ref "SENSOR") (pin "E25") (pinfunction "GND_E25") (pintype "power_in"))
      (node (ref "SENSOR") (pin "E27") (pinfunction "GND_E27") (pintype "power_in"))
      (node (ref "SENSOR") (pin "E3") (pinfunction "GND_E3") (pintype "power_in"))
      (node (ref "SENSOR") (pin "E4") (pinfunction "DIO2_E4") (pintype "output"))
      (node (ref "SENSOR") (pin "F27") (pinfunction "GND_F27") (pintype "power_in"))
      (node (ref "SENSOR") (pin "F4") (pinfunction "DIO1_F4") (pintype "output"))
      (node (ref "SENSOR") (pin "G3") (pinfunction "DIO4_G3") (pintype "output"))
      (node (ref "SENSOR") (pin "G5") (pinfunction "GND_G5") (pintype "power_in"))
      (node (ref "SENSOR") (pin "H1") (pinfunction "GND_H1") (pintype "power_in"))
      (node (ref "SENSOR") (pin "H21") (pinfunction "GND_H21") (pintype "power_in"))
      (node (ref "SENSOR") (pin "H25") (pinfunction "GND_H25") (pintype "power_in"))
      (node (ref "SENSOR") (pin "H27") (pinfunction "GND_H27") (pintype "power_in"))
      (node (ref "SENSOR") (pin "H4") (pinfunction "DIO3_H4") (pintype "output"))
      (node (ref "SENSOR") (pin "H6") (pinfunction "GND_H6") (pintype "power_in"))
      (node (ref "SENSOR") (pin "H9") (pinfunction "GND_H9") (pintype "power_in"))
      (node (ref "U1") (pin "6") (pinfunction "ANODE_6") (pintype "input"))
      (node (ref "U2") (pin "6") (pinfunction "ANODE_6") (pintype "input"))
      (node (ref "U3") (pin "2") (pinfunction "GND_2") (pintype "power_in"))
      (node (ref "U3") (pin "EP") (pinfunction "EP_EP") (pintype "power_in"))
      (node (ref "U4") (pin "16") (pinfunction "DIR2_16") (pintype "input"))
      (node (ref "U4") (pin "7") (pinfunction "~{OE}_7") (pintype "input"))
      (node (ref "U4") (pin "8") (pinfunction "GND_8") (pintype "passive"))
      (node (ref "U5") (pin "6") (pinfunction "DIR4_6") (pintype "input"))
      (node (ref "U5") (pin "7") (pinfunction "~{OE}_7") (pintype "input"))
      (node (ref "U5") (pin "8") (pinfunction "GND_8") (pintype "passive"))
      (node (ref "U6") (pin "16") (pinfunction "DIR2_16") (pintype "input"))
      (node (ref "U6") (pin "7") (pinfunction "~{OE}_7") (pintype "input"))
      (node (ref "U6") (pin "8") (pinfunction "GND_8") (pintype "passive"))
      (node (ref "U7") (pin "4") (pinfunction "GND_4") (pintype "power_in"))
      (node (ref "U7") (pin "5") (pinfunction "A2_5") (pintype "input"))
      (node (ref "U7") (pin "6") (pinfunction "A1_6") (pintype "input"))
      (node (ref "U7") (pin "7") (pinfunction "A0_7") (pintype "input"))
      (node (ref "UEP") (pin "1") (pinfunction "A0_1") (pintype "input"))
      (node (ref "UEP") (pin "2") (pinfunction "A1_2") (pintype "input"))
      (node (ref "UEP") (pin "3") (pinfunction "A2_3") (pintype "input"))
      (node (ref "UEP") (pin "4") (pinfunction "GND_4") (pintype "passive"))
      (node (ref "UEP") (pin "EP") (pinfunction "EP_EP") (pintype "passive"))
      (node (ref "UNE") (pin "4") (pinfunction "VSS_4") (pintype "power_in"))
      (node (ref "UNE") (pin "EP") (pinfunction "EP_EP") (pintype "passive"))
      (node (ref "UNN") (pin "4") (pinfunction "VSS_4") (pintype "power_in"))
      (node (ref "UNN") (pin "EP") (pinfunction "EP_EP") (pintype "passive"))
      (node (ref "UNW") (pin "4") (pinfunction "VSS_4") (pintype "power_in"))
      (node (ref "UNW") (pin "EP") (pinfunction "EP_EP") (pintype "passive"))
      (node (ref "USE") (pin "4") (pinfunction "VSS_4") (pintype "power_in"))
      (node (ref "USE") (pin "EP") (pinfunction "EP_EP") (pintype "passive"))
      (node (ref "USS") (pin "4") (pinfunction "VSS_4") (pintype "power_in"))
      (node (ref "USS") (pin "EP") (pinfunction "EP_EP") (pintype "passive"))
      (node (ref "USW") (pin "4") (pinfunction "VSS_4") (pintype "power_in"))
      (node (ref "USW") (pin "EP") (pinfunction "EP_EP") (pintype "passive"))
      (node (ref "X-NORTH") (pin "102") (pinfunction "102_102") (pintype "bidirectional"))
      (node (ref "X-NORTH") (pin "103") (pinfunction "103_103") (pintype "bidirectional"))
      (node (ref "X-NORTH") (pin "108") (pinfunction "108_108") (pintype "bidirectional"))
      (node (ref "X-NORTH") (pin "114") (pinfunction "114_114") (pintype "bidirectional"))
      (node (ref "X-NORTH") (pin "12") (pinfunction "12_12") (pintype "bidirectional"))
      (node (ref "X-NORTH") (pin "120") (pinfunction "120_120") (pintype "bidirectional"))
      (node (ref "X-NORTH") (pin "126") (pinfunction "126_126") (pintype "bidirectional"))
      (node (ref "X-NORTH") (pin "132") (pinfunction "132_132") (pintype "bidirectional"))
      (node (ref "X-NORTH") (pin "138") (pinfunction "138_138") (pintype "bidirectional"))
      (node (ref "X-NORTH") (pin "139") (pinfunction "139_139") (pintype "bidirectional"))
      (node (ref "X-NORTH") (pin "18") (pinfunction "18_18") (pintype "bidirectional"))
      (node (ref "X-NORTH") (pin "24") (pinfunction "24_24") (pintype "bidirectional"))
      (node (ref "X-NORTH") (pin "30") (pinfunction "30_30") (pintype "bidirectional"))
      (node (ref "X-NORTH") (pin "36") (pinfunction "36_36") (pintype "bidirectional"))
      (node (ref "X-NORTH") (pin "42") (pinfunction "42_42") (pintype "bidirectional"))
      (node (ref "X-NORTH") (pin "43") (pinfunction "43_43") (pintype "bidirectional"))
      (node (ref "X-NORTH") (pin "48") (pinfunction "48_48") (pintype "bidirectional"))
      (node (ref "X-NORTH") (pin "54") (pinfunction "54_54") (pintype "bidirectional"))
      (node (ref "X-NORTH") (pin "60") (pinfunction "60_60") (pintype "bidirectional"))
      (node (ref "X-NORTH") (pin "66") (pinfunction "66_66") (pintype "bidirectional"))
      (node (ref "X-NORTH") (pin "72") (pinfunction "72_72") (pintype "bidirectional"))
      (node (ref "X-NORTH") (pin "78") (pinfunction "78_78") (pintype "bidirectional"))
      (node (ref "X-NORTH") (pin "84") (pinfunction "84_84") (pintype "bidirectional"))
      (node (ref "X-NORTH") (pin "90") (pinfunction "90_90") (pintype "bidirectional"))
      (node (ref "X-NORTH") (pin "96") (pinfunction "96_96") (pintype "bidirectional"))
      (node (ref "X-SOUTH") (pin "102") (pinfunction "102_102") (pintype "bidirectional"))
      (node (ref "X-SOUTH") (pin "103") (pinfunction "103_103") (pintype "bidirectional"))
      (node (ref "X-SOUTH") (pin "108") (pinfunction "108_108") (pintype "bidirectional"))
      (node (ref "X-SOUTH") (pin "114") (pinfunction "114_114") (pintype "bidirectional"))
      (node (ref "X-SOUTH") (pin "12") (pinfunction "12_12") (pintype "bidirectional"))
      (node (ref "X-SOUTH") (pin "120") (pinfunction "120_120") (pintype "bidirectional"))
      (node (ref "X-SOUTH") (pin "126") (pinfunction "126_126") (pintype "bidirectional"))
      (node (ref "X-SOUTH") (pin "132") (pinfunction "132_132") (pintype "bidirectional"))
      (node (ref "X-SOUTH") (pin "138") (pinfunction "138_138") (pintype "bidirectional"))
      (node (ref "X-SOUTH") (pin "139") (pinfunction "139_139") (pintype "bidirectional"))
      (node (ref "X-SOUTH") (pin "18") (pinfunction "18_18") (pintype "bidirectional"))
      (node (ref "X-SOUTH") (pin "24") (pinfunction "24_24") (pintype "bidirectional"))
      (node (ref "X-SOUTH") (pin "30") (pinfunction "30_30") (pintype "bidirectional"))
      (node (ref "X-SOUTH") (pin "36") (pinfunction "36_36") (pintype "bidirectional"))
      (node (ref "X-SOUTH") (pin "42") (pinfunction "42_42") (pintype "bidirectional"))
      (node (ref "X-SOUTH") (pin "43") (pinfunction "43_43") (pintype "bidirectional"))
      (node (ref "X-SOUTH") (pin "48") (pinfunction "48_48") (pintype "bidirectional"))
      (node (ref "X-SOUTH") (pin "54") (pinfunction "54_54") (pintype "bidirectional"))
      (node (ref "X-SOUTH") (pin "60") (pinfunction "60_60") (pintype "bidirectional"))
      (node (ref "X-SOUTH") (pin "66") (pinfunction "66_66") (pintype "bidirectional"))
      (node (ref "X-SOUTH") (pin "72") (pinfunction "72_72") (pintype "bidirectional"))
      (node (ref "X-SOUTH") (pin "78") (pinfunction "78_78") (pintype "bidirectional"))
      (node (ref "X-SOUTH") (pin "84") (pinfunction "84_84") (pintype "bidirectional"))
      (node (ref "X-SOUTH") (pin "90") (pinfunction "90_90") (pintype "bidirectional"))
      (node (ref "X-SOUTH") (pin "96") (pinfunction "96_96") (pintype "bidirectional"))
    )
    (net (code "4") (name "N$42") (class "Default")
      (node (ref "SENSOR") (pin "A2") (pinfunction "TANA_A2") (pintype "output"))
    )
    (net (code "5") (name "N00_N") (class "Default")
      (node (ref "R25") (pin "2") (pinfunction "2_2") (pintype "passive"))
      (node (ref "SENSOR") (pin "E6") (pinfunction "LVDS_CLK_P_E6") (pintype "input"))
      (node (ref "X-NORTH") (pin "16") (pinfunction "16_16") (pintype "bidirectional"))
    )
    (net (code "6") (name "N00_P") (class "Default")
      (node (ref "R25") (pin "1") (pinfunction "1_1") (pintype "passive"))
      (node (ref "SENSOR") (pin "E5") (pinfunction "LVDS_CLK_N_E5") (pintype "input"))
      (node (ref "X-NORTH") (pin "14") (pinfunction "14_14") (pintype "bidirectional"))
    )
    (net (code "7") (name "N01_N") (class "Default")
      (node (ref "SENSOR") (pin "G7") (pinfunction "OUTCLK_P_G7") (pintype "output"))
      (node (ref "X-NORTH") (pin "17") (pinfunction "17_17") (pintype "bidirectional"))
    )
    (net (code "8") (name "N01_P") (class "Default")
      (node (ref "SENSOR") (pin "G6") (pinfunction "OUTCLK_N_G6") (pintype "output"))
      (node (ref "X-NORTH") (pin "15") (pinfunction "15_15") (pintype "bidirectional"))
    )
    (net (code "9") (name "N02_N") (class "Default")
      (node (ref "SENSOR") (pin "F7") (pinfunction "OUT33_P_F7") (pintype "output"))
      (node (ref "X-NORTH") (pin "22") (pinfunction "22_22") (pintype "bidirectional"))
    )
    (net (code "10") (name "N02_P") (class "Default")
      (node (ref "SENSOR") (pin "F6") (pinfunction "OUT33_N_F6") (pintype "output"))
      (node (ref "X-NORTH") (pin "20") (pinfunction "20_20") (pintype "bidirectional"))
    )
    (net (code "11") (name "N03_N") (class "Default")
      (node (ref "X-NORTH") (pin "23") (pinfunction "23_23") (pintype "bidirectional"))
    )
    (net (code "12") (name "N03_P") (class "Default")
      (node (ref "X-NORTH") (pin "21") (pinfunction "21_21") (pintype "bidirectional"))
    )
    (net (code "13") (name "N04_N") (class "Default")
      (node (ref "SENSOR") (pin "E8") (pinfunction "OUT35_P_E8") (pintype "output"))
      (node (ref "X-NORTH") (pin "28") (pinfunction "28_28") (pintype "bidirectional"))
    )
    (net (code "14") (name "N04_P") (class "Default")
      (node (ref "SENSOR") (pin "E7") (pinfunction "OUT35_N_E7") (pintype "output"))
      (node (ref "X-NORTH") (pin "26") (pinfunction "26_26") (pintype "bidirectional"))
    )
    (net (code "15") (name "N05_N") (class "Default")
      (node (ref "SENSOR") (pin "H8") (pinfunction "OUT34_P_H8") (pintype "output"))
      (node (ref "X-NORTH") (pin "29") (pinfunction "29_29") (pintype "bidirectional"))
    )
    (net (code "16") (name "N05_P") (class "Default")
      (node (ref "SENSOR") (pin "H7") (pinfunction "OUT34_N_H7") (pintype "output"))
      (node (ref "X-NORTH") (pin "27") (pinfunction "27_27") (pintype "bidirectional"))
    )
    (net (code "17") (name "N06_N") (class "Default")
      (node (ref "SENSOR") (pin "F9") (pinfunction "OUT37_P_F9") (pintype "output"))
      (node (ref "X-NORTH") (pin "34") (pinfunction "34_34") (pintype "bidirectional"))
    )
    (net (code "18") (name "N06_P") (class "Default")
      (node (ref "SENSOR") (pin "F8") (pinfunction "OUT37_N_F8") (pintype "output"))
      (node (ref "X-NORTH") (pin "32") (pinfunction "32_32") (pintype "bidirectional"))
    )
    (net (code "19") (name "N07_N") (class "Default")
      (node (ref "SENSOR") (pin "G9") (pinfunction "OUT36_P_G9") (pintype "output"))
      (node (ref "X-NORTH") (pin "35") (pinfunction "35_35") (pintype "bidirectional"))
    )
    (net (code "20") (name "N07_P") (class "Default")
      (node (ref "SENSOR") (pin "G8") (pinfunction "OUT36_N_G8") (pintype "output"))
      (node (ref "X-NORTH") (pin "33") (pinfunction "33_33") (pintype "bidirectional"))
    )
    (net (code "21") (name "N08_N") (class "Default")
      (node (ref "SENSOR") (pin "E10") (pinfunction "OUT38_P_E10") (pintype "output"))
      (node (ref "X-NORTH") (pin "40") (pinfunction "40_40") (pintype "bidirectional"))
    )
    (net (code "22") (name "N08_P") (class "Default")
      (node (ref "SENSOR") (pin "E9") (pinfunction "OUT38_N_E9") (pintype "output"))
      (node (ref "X-NORTH") (pin "38") (pinfunction "38_38") (pintype "bidirectional"))
    )
    (net (code "23") (name "N09_N") (class "Default")
      (node (ref "SENSOR") (pin "G11") (pinfunction "OUT39_P_G11") (pintype "output"))
      (node (ref "X-NORTH") (pin "41") (pinfunction "41_41") (pintype "bidirectional"))
    )
    (net (code "24") (name "N09_P") (class "Default")
      (node (ref "SENSOR") (pin "G10") (pinfunction "OUT39_N_G10") (pintype "output"))
      (node (ref "X-NORTH") (pin "39") (pinfunction "39_39") (pintype "bidirectional"))
    )
    (net (code "25") (name "N10_N") (class "Default")
      (node (ref "SENSOR") (pin "F11") (pinfunction "OUT40_P_F11") (pintype "output"))
      (node (ref "X-NORTH") (pin "46") (pinfunction "46_46") (pintype "bidirectional"))
    )
    (net (code "26") (name "N10_P") (class "Default")
      (node (ref "SENSOR") (pin "F10") (pinfunction "OUT40_N_F10") (pintype "output"))
      (node (ref "X-NORTH") (pin "44") (pinfunction "44_44") (pintype "bidirectional"))
    )
    (net (code "27") (name "N11_N") (class "Default")
      (node (ref "SENSOR") (pin "H12") (pinfunction "OUT41_P_H12") (pintype "output"))
      (node (ref "X-NORTH") (pin "47") (pinfunction "47_47") (pintype "bidirectional"))
    )
    (net (code "28") (name "N11_P") (class "Default")
      (node (ref "SENSOR") (pin "H11") (pinfunction "OUT41_N_H11") (pintype "output"))
      (node (ref "X-NORTH") (pin "45") (pinfunction "45_45") (pintype "bidirectional"))
    )
    (net (code "29") (name "N12_N") (class "Default")
      (node (ref "SENSOR") (pin "E12") (pinfunction "OUT42_P_E12") (pintype "output"))
      (node (ref "X-NORTH") (pin "52") (pinfunction "52_52") (pintype "bidirectional"))
    )
    (net (code "30") (name "N12_P") (class "Default")
      (node (ref "SENSOR") (pin "E11") (pinfunction "OUT42_N_E11") (pintype "output"))
      (node (ref "X-NORTH") (pin "50") (pinfunction "50_50") (pintype "bidirectional"))
    )
    (net (code "31") (name "N13_N") (class "Default")
      (node (ref "SENSOR") (pin "G13") (pinfunction "OUT43_P_G13") (pintype "output"))
      (node (ref "X-NORTH") (pin "53") (pinfunction "53_53") (pintype "bidirectional"))
    )
    (net (code "32") (name "N13_P") (class "Default")
      (node (ref "SENSOR") (pin "G12") (pinfunction "OUT43_N_G12") (pintype "output"))
      (node (ref "X-NORTH") (pin "51") (pinfunction "51_51") (pintype "bidirectional"))
    )
    (net (code "33") (name "N14_N") (class "Default")
      (node (ref "SENSOR") (pin "F13") (pinfunction "OUT44_P_F13") (pintype "output"))
      (node (ref "X-NORTH") (pin "58") (pinfunction "58_58") (pintype "bidirectional"))
    )
    (net (code "34") (name "N14_P") (class "Default")
      (node (ref "SENSOR") (pin "F12") (pinfunction "OUT44_N_F12") (pintype "output"))
      (node (ref "X-NORTH") (pin "56") (pinfunction "56_56") (pintype "bidirectional"))
    )
    (net (code "35") (name "N15_N") (class "Default")
      (node (ref "SENSOR") (pin "H14") (pinfunction "OUT45_P_H14") (pintype "output"))
      (node (ref "X-NORTH") (pin "59") (pinfunction "59_59") (pintype "bidirectional"))
    )
    (net (code "36") (name "N15_P") (class "Default")
      (node (ref "SENSOR") (pin "H13") (pinfunction "OUT45_N_H13") (pintype "output"))
      (node (ref "X-NORTH") (pin "57") (pinfunction "57_57") (pintype "bidirectional"))
    )
    (net (code "37") (name "N16_N") (class "Default")
      (node (ref "SENSOR") (pin "E14") (pinfunction "OUT46_P_E14") (pintype "output"))
      (node (ref "X-NORTH") (pin "64") (pinfunction "64_64") (pintype "bidirectional"))
    )
    (net (code "38") (name "N16_P") (class "Default")
      (node (ref "SENSOR") (pin "E13") (pinfunction "OUT46_N_E13") (pintype "output"))
      (node (ref "X-NORTH") (pin "62") (pinfunction "62_62") (pintype "bidirectional"))
    )
    (net (code "39") (name "N17_N") (class "Default")
      (node (ref "SENSOR") (pin "G15") (pinfunction "OUT47_P_G15") (pintype "output"))
      (node (ref "X-NORTH") (pin "65") (pinfunction "65_65") (pintype "bidirectional"))
    )
    (net (code "40") (name "N17_P") (class "Default")
      (node (ref "SENSOR") (pin "G14") (pinfunction "OUT47_N_G14") (pintype "output"))
      (node (ref "X-NORTH") (pin "63") (pinfunction "63_63") (pintype "bidirectional"))
    )
    (net (code "41") (name "N18_N") (class "Default")
      (node (ref "SENSOR") (pin "F15") (pinfunction "OUT48_P_F15") (pintype "output"))
      (node (ref "X-NORTH") (pin "70") (pinfunction "70_70") (pintype "bidirectional"))
    )
    (net (code "42") (name "N18_P") (class "Default")
      (node (ref "SENSOR") (pin "F14") (pinfunction "OUT48_N_F14") (pintype "output"))
      (node (ref "X-NORTH") (pin "68") (pinfunction "68_68") (pintype "bidirectional"))
    )
    (net (code "43") (name "N19_N") (class "Default")
      (node (ref "SENSOR") (pin "G17") (pinfunction "OUT50_P_G17") (pintype "output"))
      (node (ref "X-NORTH") (pin "71") (pinfunction "71_71") (pintype "bidirectional"))
    )
    (net (code "44") (name "N19_P") (class "Default")
      (node (ref "SENSOR") (pin "G16") (pinfunction "OUT50_N_G16") (pintype "output"))
      (node (ref "X-NORTH") (pin "69") (pinfunction "69_69") (pintype "bidirectional"))
    )
    (net (code "45") (name "N20_N") (class "Default")
      (node (ref "SENSOR") (pin "F17") (pinfunction "OUT49_P_F17") (pintype "output"))
      (node (ref "X-NORTH") (pin "76") (pinfunction "76_76") (pintype "bidirectional"))
    )
    (net (code "46") (name "N20_P") (class "Default")
      (node (ref "SENSOR") (pin "F16") (pinfunction "OUT49_N_F16") (pintype "output"))
      (node (ref "X-NORTH") (pin "74") (pinfunction "74_74") (pintype "bidirectional"))
    )
    (net (code "47") (name "N21_N") (class "Default")
      (node (ref "SENSOR") (pin "H18") (pinfunction "OUT52_P_H18") (pintype "output"))
      (node (ref "X-NORTH") (pin "77") (pinfunction "77_77") (pintype "bidirectional"))
    )
    (net (code "48") (name "N21_P") (class "Default")
      (node (ref "SENSOR") (pin "H17") (pinfunction "OUT52_N_H17") (pintype "output"))
      (node (ref "X-NORTH") (pin "75") (pinfunction "75_75") (pintype "bidirectional"))
    )
    (net (code "49") (name "N22_N") (class "Default")
      (node (ref "SENSOR") (pin "E18") (pinfunction "OUT51_P_E18") (pintype "output"))
      (node (ref "X-NORTH") (pin "82") (pinfunction "82_82") (pintype "bidirectional"))
    )
    (net (code "50") (name "N22_P") (class "Default")
      (node (ref "SENSOR") (pin "E17") (pinfunction "OUT51_N_E17") (pintype "output"))
      (node (ref "X-NORTH") (pin "80") (pinfunction "80_80") (pintype "bidirectional"))
    )
    (net (code "51") (name "N23_N") (class "Default")
      (node (ref "SENSOR") (pin "G19") (pinfunction "OUT54_P_G19") (pintype "output"))
      (node (ref "X-NORTH") (pin "83") (pinfunction "83_83") (pintype "bidirectional"))
    )
    (net (code "52") (name "N23_P") (class "Default")
      (node (ref "SENSOR") (pin "G18") (pinfunction "OUT54_N_G18") (pintype "output"))
      (node (ref "X-NORTH") (pin "81") (pinfunction "81_81") (pintype "bidirectional"))
    )
    (net (code "53") (name "N24_N") (class "Default")
      (node (ref "SENSOR") (pin "F19") (pinfunction "OUT53_P_F19") (pintype "output"))
      (node (ref "X-NORTH") (pin "88") (pinfunction "88_88") (pintype "bidirectional"))
    )
    (net (code "54") (name "N24_P") (class "Default")
      (node (ref "SENSOR") (pin "F18") (pinfunction "OUT53_N_F18") (pintype "output"))
      (node (ref "X-NORTH") (pin "86") (pinfunction "86_86") (pintype "bidirectional"))
    )
    (net (code "55") (name "N25_N") (class "Default")
      (node (ref "SENSOR") (pin "H20") (pinfunction "OUT56_P_H20") (pintype "output"))
      (node (ref "X-NORTH") (pin "89") (pinfunction "89_89") (pintype "bidirectional"))
    )
    (net (code "56") (name "N25_P") (class "Default")
      (node (ref "SENSOR") (pin "H19") (pinfunction "OUT56_N_H19") (pintype "output"))
      (node (ref "X-NORTH") (pin "87") (pinfunction "87_87") (pintype "bidirectional"))
    )
    (net (code "57") (name "N26_N") (class "Default")
      (node (ref "SENSOR") (pin "E20") (pinfunction "OUT55_P_E20") (pintype "output"))
      (node (ref "X-NORTH") (pin "94") (pinfunction "94_94") (pintype "bidirectional"))
    )
    (net (code "58") (name "N26_P") (class "Default")
      (node (ref "SENSOR") (pin "E19") (pinfunction "OUT55_N_E19") (pintype "output"))
      (node (ref "X-NORTH") (pin "92") (pinfunction "92_92") (pintype "bidirectional"))
    )
    (net (code "59") (name "N27_N") (class "Default")
      (node (ref "SENSOR") (pin "G21") (pinfunction "OUT58_P_G21") (pintype "output"))
      (node (ref "X-NORTH") (pin "95") (pinfunction "95_95") (pintype "bidirectional"))
    )
    (net (code "60") (name "N27_P") (class "Default")
      (node (ref "SENSOR") (pin "G20") (pinfunction "OUT58_N_G20") (pintype "output"))
      (node (ref "X-NORTH") (pin "93") (pinfunction "93_93") (pintype "bidirectional"))
    )
    (net (code "61") (name "N28_N") (class "Default")
      (node (ref "SENSOR") (pin "F21") (pinfunction "OUT57_P_F21") (pintype "output"))
      (node (ref "X-NORTH") (pin "100") (pinfunction "100_100") (pintype "bidirectional"))
    )
    (net (code "62") (name "N28_P") (class "Default")
      (node (ref "SENSOR") (pin "F20") (pinfunction "OUT57_N_F20") (pintype "output"))
      (node (ref "X-NORTH") (pin "98") (pinfunction "98_98") (pintype "bidirectional"))
    )
    (net (code "63") (name "N29_N") (class "Default")
      (node (ref "SENSOR") (pin "G23") (pinfunction "OUT61_P_G23") (pintype "output"))
      (node (ref "X-NORTH") (pin "101") (pinfunction "101_101") (pintype "bidirectional"))
    )
    (net (code "64") (name "N29_P") (class "Default")
      (node (ref "SENSOR") (pin "G22") (pinfunction "OUT61_N_G22") (pintype "output"))
      (node (ref "X-NORTH") (pin "99") (pinfunction "99_99") (pintype "bidirectional"))
    )
    (net (code "65") (name "N30_N") (class "Default")
      (node (ref "SENSOR") (pin "E22") (pinfunction "OUT59_P_E22") (pintype "output"))
      (node (ref "X-NORTH") (pin "106") (pinfunction "106_106") (pintype "bidirectional"))
    )
    (net (code "66") (name "N30_P") (class "Default")
      (node (ref "SENSOR") (pin "E21") (pinfunction "OUT59_N_E21") (pintype "output"))
      (node (ref "X-NORTH") (pin "104") (pinfunction "104_104") (pintype "bidirectional"))
    )
    (net (code "67") (name "N31_N") (class "Default")
      (node (ref "SENSOR") (pin "H24") (pinfunction "OUT63_P_H24") (pintype "output"))
      (node (ref "X-NORTH") (pin "107") (pinfunction "107_107") (pintype "bidirectional"))
    )
    (net (code "68") (name "N31_P") (class "Default")
      (node (ref "SENSOR") (pin "H23") (pinfunction "OUT63_N_H23") (pintype "output"))
      (node (ref "X-NORTH") (pin "105") (pinfunction "105_105") (pintype "bidirectional"))
    )
    (net (code "69") (name "N32_N") (class "Default")
      (node (ref "SENSOR") (pin "F23") (pinfunction "OUT60_P_F23") (pintype "output"))
      (node (ref "X-NORTH") (pin "112") (pinfunction "112_112") (pintype "bidirectional"))
    )
    (net (code "70") (name "N32_P") (class "Default")
      (node (ref "SENSOR") (pin "F22") (pinfunction "OUT60_N_F22") (pintype "output"))
      (node (ref "X-NORTH") (pin "110") (pinfunction "110_110") (pintype "bidirectional"))
    )
    (net (code "71") (name "N33_N") (class "Default")
      (node (ref "SENSOR") (pin "G25") (pinfunction "OUT64_P_G25") (pintype "output"))
      (node (ref "X-NORTH") (pin "113") (pinfunction "113_113") (pintype "bidirectional"))
    )
    (net (code "72") (name "N33_P") (class "Default")
      (node (ref "SENSOR") (pin "G24") (pinfunction "OUT64_N_G24") (pintype "output"))
      (node (ref "X-NORTH") (pin "111") (pinfunction "111_111") (pintype "bidirectional"))
    )
    (net (code "73") (name "N34_N") (class "Default")
      (node (ref "SENSOR") (pin "E24") (pinfunction "OUT62_P_E24") (pintype "output"))
      (node (ref "X-NORTH") (pin "118") (pinfunction "118_118") (pintype "bidirectional"))
    )
    (net (code "74") (name "N34_P") (class "Default")
      (node (ref "SENSOR") (pin "E23") (pinfunction "OUT62_N_E23") (pintype "output"))
      (node (ref "X-NORTH") (pin "116") (pinfunction "116_116") (pintype "bidirectional"))
    )
    (net (code "75") (name "N35_N") (class "Default")
      (node (ref "U6") (pin "4") (pinfunction "A4_4") (pintype "bidirectional"))
      (node (ref "X-NORTH") (pin "119") (pinfunction "119_119") (pintype "bidirectional"))
    )
    (net (code "76") (name "N35_P") (class "Default")
      (node (ref "U6") (pin "3") (pinfunction "A3_3") (pintype "bidirectional"))
      (node (ref "X-NORTH") (pin "117") (pinfunction "117_117") (pintype "bidirectional"))
    )
    (net (code "77") (name "N36_N") (class "Default")
      (node (ref "X-NORTH") (pin "124") (pinfunction "124_124") (pintype "bidirectional"))
    )
    (net (code "78") (name "N36_P") (class "Default")
      (node (ref "X-NORTH") (pin "122") (pinfunction "122_122") (pintype "bidirectional"))
    )
    (net (code "79") (name "N37_N") (class "Default")
      (node (ref "U5") (pin "3") (pinfunction "A3_3") (pintype "bidirectional"))
      (node (ref "X-NORTH") (pin "125") (pinfunction "125_125") (pintype "bidirectional"))
    )
    (net (code "80") (name "N37_P") (class "Default")
      (node (ref "U5") (pin "4") (pinfunction "A4_4") (pintype "bidirectional"))
      (node (ref "X-NORTH") (pin "123") (pinfunction "123_123") (pintype "bidirectional"))
    )
    (net (code "81") (name "N38_N") (class "Default")
      (node (ref "U6") (pin "2") (pinfunction "A2_2") (pintype "bidirectional"))
      (node (ref "X-NORTH") (pin "130") (pinfunction "130_130") (pintype "bidirectional"))
    )
    (net (code "82") (name "N38_P") (class "Default")
      (node (ref "U6") (pin "1") (pinfunction "A1_1") (pintype "bidirectional"))
      (node (ref "X-NORTH") (pin "128") (pinfunction "128_128") (pintype "bidirectional"))
    )
    (net (code "83") (name "N39_N") (class "Default")
      (node (ref "U5") (pin "1") (pinfunction "A1_1") (pintype "bidirectional"))
      (node (ref "X-NORTH") (pin "131") (pinfunction "131_131") (pintype "bidirectional"))
    )
    (net (code "84") (name "N39_P") (class "Default")
      (node (ref "U5") (pin "2") (pinfunction "A2_2") (pintype "bidirectional"))
      (node (ref "X-NORTH") (pin "129") (pinfunction "129_129") (pintype "bidirectional"))
    )
    (net (code "85") (name "N_CHK_EN") (class "Default")
      (node (ref "X-NORTH") (pin "8") (pinfunction "8_8") (pintype "bidirectional"))
    )
    (net (code "86") (name "N_CHK_V") (class "Default")
      (node (ref "C2") (pin "1") (pinfunction "1_1") (pintype "passive"))
      (node (ref "C3") (pin "1") (pinfunction "1_1") (pintype "passive"))
      (node (ref "C4") (pin "1") (pinfunction "1_1") (pintype "passive"))
      (node (ref "R19") (pin "1") (pinfunction "1_1") (pintype "passive"))
      (node (ref "TP1") (pin "TP") (pinfunction "TP_TP") (pintype "input"))
      (node (ref "UNE") (pin "8") (pinfunction "VDD_8") (pintype "power_in"))
      (node (ref "UNN") (pin "8") (pinfunction "VDD_8") (pintype "power_in"))
      (node (ref "UNW") (pin "8") (pinfunction "VDD_8") (pintype "power_in"))
      (node (ref "X-NORTH") (pin "10") (pinfunction "10_10") (pintype "bidirectional"))
    )
    (net (code "87") (name "N_I2C_EN") (class "Default")
      (node (ref "X-NORTH") (pin "137") (pinfunction "137_137") (pintype "bidirectional"))
    )
    (net (code "88") (name "N_I2C_V") (class "Default")
      (node (ref "C1") (pin "1") (pinfunction "1_1") (pintype "passive"))
      (node (ref "R1X") (pin "1") (pinfunction "1_1") (pintype "passive"))
      (node (ref "UEP") (pin "8") (pinfunction "VCC_8") (pintype "power_in"))
      (node (ref "X-NORTH") (pin "135") (pinfunction "135_135") (pintype "bidirectional"))
    )
    (net (code "89") (name "N_REF") (class "Default")
      (node (ref "R19") (pin "2") (pinfunction "2_2") (pintype "passive"))
      (node (ref "TP2") (pin "TP") (pinfunction "TP_TP") (pintype "input"))
      (node (ref "U1") (pin "1") (pinfunction "CATHODE_1") (pintype "output"))
      (node (ref "U1") (pin "3") (pinfunction "REF_3") (pintype "input"))
      (node (ref "UNE") (pin "2") (pinfunction "VINA-_2") (pintype "input"))
      (node (ref "UNE") (pin "5") (pinfunction "VINB+_5") (pintype "input"))
      (node (ref "UNN") (pin "2") (pinfunction "VINA-_2") (pintype "input"))
      (node (ref "UNN") (pin "5") (pinfunction "VINB+_5") (pintype "input"))
      (node (ref "UNW") (pin "2") (pinfunction "VINA-_2") (pintype "input"))
      (node (ref "UNW") (pin "5") (pinfunction "VINB+_5") (pintype "input"))
    )
    (net (code "90") (name "N_SCK") (class "Default")
      (node (ref "U4") (pin "4") (pinfunction "A4_4") (pintype "bidirectional"))
      (node (ref "X-NORTH") (pin "144") (pinfunction "144_144") (pintype "bidirectional"))
    )
    (net (code "91") (name "N_SCL") (class "Default")
      (node (ref "UEP") (pin "6") (pinfunction "SCL_6") (pintype "input"))
      (node (ref "X-NORTH") (pin "143") (pinfunction "143_143") (pintype "bidirectional"))
    )
    (net (code "92") (name "N_SDA") (class "Default")
      (node (ref "UEP") (pin "5") (pinfunction "SDA_5") (pintype "bidirectional"))
      (node (ref "X-NORTH") (pin "141") (pinfunction "141_141") (pintype "bidirectional"))
    )
    (net (code "93") (name "N_SDI") (class "Default")
      (node (ref "U4") (pin "2") (pinfunction "A2_2") (pintype "bidirectional"))
      (node (ref "X-NORTH") (pin "140") (pinfunction "140_140") (pintype "bidirectional"))
    )
    (net (code "94") (name "N_SDO") (class "Default")
      (node (ref "U4") (pin "3") (pinfunction "A3_3") (pintype "bidirectional"))
      (node (ref "X-NORTH") (pin "142") (pinfunction "142_142") (pintype "bidirectional"))
    )
    (net (code "95") (name "N_SPI_EN") (class "Default")
      (node (ref "U4") (pin "1") (pinfunction "A1_1") (pintype "bidirectional"))
      (node (ref "X-NORTH") (pin "136") (pinfunction "136_136") (pintype "bidirectional"))
    )
    (net (code "96") (name "N_SPI_V") (class "Default")
      (node (ref "C59") (pin "1") (pinfunction "1_1") (pintype "passive"))
      (node (ref "U4") (pin "14") (pinfunction "VCCA_14") (pintype "power_in"))
      (node (ref "U4") (pin "15") (pinfunction "DIR1_15") (pintype "input"))
      (node (ref "U4") (pin "5") (pinfunction "DIR3_5") (pintype "input"))
      (node (ref "U4") (pin "6") (pinfunction "DIR4_6") (pintype "input"))
      (node (ref "X-NORTH") (pin "134") (pinfunction "134_134") (pintype "bidirectional"))
    )
    (net (code "97") (name "N_VE") (class "Default")
      (node (ref "C22") (pin "1") (pinfunction "1_1") (pintype "passive"))
      (node (ref "C23") (pin "1") (pinfunction "1_1") (pintype "passive"))
      (node (ref "C24") (pin "1") (pinfunction "1_1") (pintype "passive"))
      (node (ref "C25") (pin "1") (pinfunction "1_1") (pintype "passive"))
      (node (ref "C26") (pin "1") (pinfunction "1_1") (pintype "passive"))
      (node (ref "C27") (pin "1") (pinfunction "1_1") (pintype "passive"))
      (node (ref "C28") (pin "1") (pinfunction "1_1") (pintype "passive"))
      (node (ref "C50") (pin "1") (pinfunction "1_1") (pintype "passive"))
      (node (ref "C51") (pin "1") (pinfunction "1_1") (pintype "passive"))
      (node (ref "C52") (pin "1") (pinfunction "1_1") (pintype "passive"))
      (node (ref "C53") (pin "1") (pinfunction "1_1") (pintype "passive"))
      (node (ref "C54") (pin "1") (pinfunction "1_1") (pintype "passive"))
      (node (ref "C55") (pin "1") (pinfunction "1_1") (pintype "passive"))
      (node (ref "C56") (pin "1") (pinfunction "1_1") (pintype "passive"))
      (node (ref "C67") (pin "1") (pinfunction "1_1") (pintype "passive"))
      (node (ref "C69") (pin "1") (pinfunction "1_1") (pintype "passive"))
      (node (ref "C75") (pin "1") (pinfunction "1_1") (pintype "passive"))
      (node (ref "C76") (pin "1") (pinfunction "1_1") (pintype "passive"))
      (node (ref "C77") (pin "1") (pinfunction "1_1") (pintype "passive"))
      (node (ref "C84") (pin "1") (pinfunction "1_1") (pintype "passive"))
      (node (ref "C85") (pin "1") (pinfunction "1_1") (pintype "passive"))
      (node (ref "C86") (pin "1") (pinfunction "1_1") (pintype "passive"))
      (node (ref "C93") (pin "1") (pinfunction "1_1") (pintype "passive"))
      (node (ref "SENSOR") (pin "C26") (pinfunction "VDD33_C26") (pintype "power_in"))
      (node (ref "SENSOR") (pin "C27") (pinfunction "VDD33_C27") (pintype "power_in"))
      (node (ref "SENSOR") (pin "D26") (pinfunction "VDD33_D26") (pintype "power_in"))
      (node (ref "SENSOR") (pin "D3") (pinfunction "VDD33_D3") (pintype "power_in"))
      (node (ref "SENSOR") (pin "E26") (pinfunction "VDD33_E26") (pintype "power_in"))
      (node (ref "SENSOR") (pin "F26") (pinfunction "VDD33_F26") (pintype "power_in"))
      (node (ref "SENSOR") (pin "F5") (pinfunction "VDD33_F5") (pintype "power_in"))
      (node (ref "TP7") (pin "TP") (pinfunction "TP_TP") (pintype "input"))
      (node (ref "U4") (pin "13") (pinfunction "VCCB_13") (pintype "power_in"))
      (node (ref "U5") (pin "13") (pinfunction "VCCB_13") (pintype "power_in"))
      (node (ref "U6") (pin "13") (pinfunction "VCCB_13") (pintype "power_in"))
      (node (ref "X-NORTH") (pin "109") (pinfunction "109_109") (pintype "bidirectional"))
      (node (ref "X-NORTH") (pin "115") (pinfunction "115_115") (pintype "bidirectional"))
      (node (ref "X-NORTH") (pin "121") (pinfunction "121_121") (pintype "bidirectional"))
      (node (ref "X-NORTH") (pin "127") (pinfunction "127_127") (pintype "bidirectional"))
      (node (ref "X-NORTH") (pin "133") (pinfunction "133_133") (pintype "bidirectional"))
    )
    (net (code "98") (name "N_VE_CV") (class "Default")
      (node (ref "C10") (pin "1") (pinfunction "1_1") (pintype "passive"))
      (node (ref "R7") (pin "1") (pinfunction "1_1") (pintype "passive"))
      (node (ref "X-NORTH") (pin "6") (pinfunction "6_6") (pintype "bidirectional"))
    )
    (net (code "99") (name "N_VE_OV") (class "Default")
      (node (ref "UNE") (pin "7") (pinfunction "OUTB_7") (pintype "output"))
      (node (ref "X-NORTH") (pin "5") (pinfunction "5_5") (pintype "bidirectional"))
    )
    (net (code "100") (name "N_VE_UV") (class "Default")
      (node (ref "UNE") (pin "1") (pinfunction "OUTA_1") (pintype "output"))
      (node (ref "X-NORTH") (pin "11") (pinfunction "11_11") (pintype "bidirectional"))
    )
    (net (code "101") (name "N_VN") (class "Default")
      (node (ref "C31") (pin "1") (pinfunction "1_1") (pintype "passive"))
      (node (ref "C32") (pin "1") (pinfunction "1_1") (pintype "passive"))
      (node (ref "C33") (pin "1") (pinfunction "1_1") (pintype "passive"))
      (node (ref "C34") (pin "1") (pinfunction "1_1") (pintype "passive"))
      (node (ref "C35") (pin "1") (pinfunction "1_1") (pintype "passive"))
      (node (ref "C36") (pin "1") (pinfunction "1_1") (pintype "passive"))
      (node (ref "C37") (pin "1") (pinfunction "1_1") (pintype "passive"))
      (node (ref "C38") (pin "1") (pinfunction "1_1") (pintype "passive"))
      (node (ref "C39") (pin "1") (pinfunction "1_1") (pintype "passive"))
      (node (ref "C40") (pin "1") (pinfunction "1_1") (pintype "passive"))
      (node (ref "C41") (pin "1") (pinfunction "1_1") (pintype "passive"))
      (node (ref "C42") (pin "1") (pinfunction "1_1") (pintype "passive"))
      (node (ref "C43") (pin "1") (pinfunction "1_1") (pintype "passive"))
      (node (ref "C44") (pin "1") (pinfunction "1_1") (pintype "passive"))
      (node (ref "C68") (pin "1") (pinfunction "1_1") (pintype "passive"))
      (node (ref "C70") (pin "1") (pinfunction "1_1") (pintype "passive"))
      (node (ref "C78") (pin "1") (pinfunction "1_1") (pintype "passive"))
      (node (ref "C79") (pin "1") (pinfunction "1_1") (pintype "passive"))
      (node (ref "C80") (pin "1") (pinfunction "1_1") (pintype "passive"))
      (node (ref "C87") (pin "1") (pinfunction "1_1") (pintype "passive"))
      (node (ref "C88") (pin "1") (pinfunction "1_1") (pintype "passive"))
      (node (ref "C89") (pin "1") (pinfunction "1_1") (pintype "passive"))
      (node (ref "SENSOR") (pin "A10") (pinfunction "VDD18_A10") (pintype "power_in"))
      (node (ref "SENSOR") (pin "A15") (pinfunction "VDD18_A15") (pintype "power_in"))
      (node (ref "SENSOR") (pin "A16") (pinfunction "VDD18_A16") (pintype "power_in"))
      (node (ref "SENSOR") (pin "A22") (pinfunction "VDD18_A22") (pintype "power_in"))
      (node (ref "SENSOR") (pin "A26") (pinfunction "VDD18_A26") (pintype "power_in"))
      (node (ref "SENSOR") (pin "A27") (pinfunction "VDD18_A27") (pintype "power_in"))
      (node (ref "SENSOR") (pin "B4") (pinfunction "VDD18_B4") (pintype "power_in"))
      (node (ref "SENSOR") (pin "E1") (pinfunction "VDD18_PLL_E1") (pintype "power_in"))
      (node (ref "SENSOR") (pin "H10") (pinfunction "VDD18_H10") (pintype "power_in"))
      (node (ref "SENSOR") (pin "H15") (pinfunction "VDD18_H15") (pintype "power_in"))
      (node (ref "SENSOR") (pin "H16") (pinfunction "VDD18_H16") (pintype "power_in"))
      (node (ref "SENSOR") (pin "H22") (pinfunction "VDD18_H22") (pintype "power_in"))
      (node (ref "SENSOR") (pin "H26") (pinfunction "VDD18_H26") (pintype "power_in"))
      (node (ref "SENSOR") (pin "H5") (pinfunction "VDD18_H5") (pintype "power_in"))
      (node (ref "TP5") (pin "TP") (pinfunction "TP_TP") (pintype "input"))
      (node (ref "U5") (pin "14") (pinfunction "VCCA_14") (pintype "power_in"))
      (node (ref "U5") (pin "15") (pinfunction "DIR1_15") (pintype "input"))
      (node (ref "U5") (pin "16") (pinfunction "DIR2_16") (pintype "input"))
      (node (ref "U5") (pin "5") (pinfunction "DIR3_5") (pintype "input"))
      (node (ref "U6") (pin "14") (pinfunction "VCCA_14") (pintype "power_in"))
      (node (ref "U6") (pin "15") (pinfunction "DIR1_15") (pintype "input"))
      (node (ref "U6") (pin "5") (pinfunction "DIR3_5") (pintype "input"))
      (node (ref "U6") (pin "6") (pinfunction "DIR4_6") (pintype "input"))
      (node (ref "X-NORTH") (pin "49") (pinfunction "49_49") (pintype "bidirectional"))
      (node (ref "X-NORTH") (pin "55") (pinfunction "55_55") (pintype "bidirectional"))
      (node (ref "X-NORTH") (pin "61") (pinfunction "61_61") (pintype "bidirectional"))
      (node (ref "X-NORTH") (pin "67") (pinfunction "67_67") (pintype "bidirectional"))
      (node (ref "X-NORTH") (pin "73") (pinfunction "73_73") (pintype "bidirectional"))
      (node (ref "X-NORTH") (pin "79") (pinfunction "79_79") (pintype "bidirectional"))
      (node (ref "X-NORTH") (pin "85") (pinfunction "85_85") (pintype "bidirectional"))
      (node (ref "X-NORTH") (pin "91") (pinfunction "91_91") (pintype "bidirectional"))
      (node (ref "X-NORTH") (pin "97") (pinfunction "97_97") (pintype "bidirectional"))
    )
    (net (code "102") (name "N_VN_CV") (class "Default")
      (node (ref "C9") (pin "1") (pinfunction "1_1") (pintype "passive"))
      (node (ref "R4") (pin "1") (pinfunction "1_1") (pintype "passive"))
      (node (ref "X-NORTH") (pin "4") (pinfunction "4_4") (pintype "bidirectional"))
    )
    (net (code "103") (name "N_VN_OV") (class "Default")
      (node (ref "UNN") (pin "7") (pinfunction "OUTB_7") (pintype "output"))
      (node (ref "X-NORTH") (pin "3") (pinfunction "3_3") (pintype "bidirectional"))
    )
    (net (code "104") (name "N_VN_UV") (class "Default")
      (node (ref "UNN") (pin "1") (pinfunction "OUTA_1") (pintype "output"))
      (node (ref "X-NORTH") (pin "9") (pinfunction "9_9") (pintype "bidirectional"))
    )
    (net (code "105") (name "N_VW") (class "Default")
      (node (ref "C57") (pin "1") (pinfunction "1_1") (pintype "passive"))
      (node (ref "C58") (pin "1") (pinfunction "1_1") (pintype "passive"))
      (node (ref "C92") (pin "1") (pinfunction "1_1") (pintype "passive"))
      (node (ref "SENSOR") (pin "E2") (pinfunction "VDD_RES_E2") (pintype "power_in"))
      (node (ref "SENSOR") (pin "G4") (pinfunction "VDD_RES_G4") (pintype "power_in"))
      (node (ref "TP8") (pin "TP") (pinfunction "TP_TP") (pintype "input"))
      (node (ref "X-NORTH") (pin "13") (pinfunction "13_13") (pintype "bidirectional"))
      (node (ref "X-NORTH") (pin "19") (pinfunction "19_19") (pintype "bidirectional"))
      (node (ref "X-NORTH") (pin "25") (pinfunction "25_25") (pintype "bidirectional"))
      (node (ref "X-NORTH") (pin "31") (pinfunction "31_31") (pintype "bidirectional"))
      (node (ref "X-NORTH") (pin "37") (pinfunction "37_37") (pintype "bidirectional"))
    )
    (net (code "106") (name "N_VW_CV") (class "Default")
      (node (ref "C8") (pin "1") (pinfunction "1_1") (pintype "passive"))
      (node (ref "R1") (pin "1") (pinfunction "1_1") (pintype "passive"))
      (node (ref "X-NORTH") (pin "2") (pinfunction "2_2") (pintype "bidirectional"))
    )
    (net (code "107") (name "N_VW_OV") (class "Default")
      (node (ref "UNW") (pin "7") (pinfunction "OUTB_7") (pintype "output"))
      (node (ref "X-NORTH") (pin "1") (pinfunction "1_1") (pintype "bidirectional"))
    )
    (net (code "108") (name "N_VW_UV") (class "Default")
      (node (ref "UNW") (pin "1") (pinfunction "OUTA_1") (pintype "output"))
      (node (ref "X-NORTH") (pin "7") (pinfunction "7_7") (pintype "bidirectional"))
    )
    (net (code "109") (name "Net-(SENSORB-CMDN)") (class "Default")
      (node (ref "C61") (pin "1") (pinfunction "1_1") (pintype "passive"))
      (node (ref "SENSOR") (pin "F1") (pinfunction "CMDN_F1") (pintype "bidirectional"))
    )
    (net (code "110") (name "Net-(SENSORB-CMDP)") (class "Default")
      (node (ref "C22") (pin "2") (pinfunction "2_2") (pintype "passive"))
      (node (ref "SENSOR") (pin "F2") (pinfunction "CMDP_F2") (pintype "bidirectional"))
    )
    (net (code "111") (name "Net-(SENSORB-CMDP_COMP)") (class "Default")
      (node (ref "C28") (pin "2") (pinfunction "2_2") (pintype "passive"))
      (node (ref "SENSOR") (pin "H3") (pinfunction "CMDP_COMP_H3") (pintype "bidirectional"))
    )
    (net (code "112") (name "Net-(SENSORB-CMDP_COMP_INV)") (class "Default")
      (node (ref "C27") (pin "2") (pinfunction "2_2") (pintype "passive"))
      (node (ref "SENSOR") (pin "F3") (pinfunction "CMDP_COMP_INV_F3") (pintype "bidirectional"))
    )
    (net (code "113") (name "Net-(SENSORB-CMD_COLAMP)") (class "Default")
      (node (ref "C25") (pin "2") (pinfunction "2_2") (pintype "passive"))
      (node (ref "SENSOR") (pin "C6") (pinfunction "CMD_COLAMP_C6") (pintype "bidirectional"))
    )
    (net (code "114") (name "Net-(SENSORB-CMD_COL_LOAD)") (class "Default")
      (node (ref "C23") (pin "2") (pinfunction "2_2") (pintype "passive"))
      (node (ref "SENSOR") (pin "B1") (pinfunction "CMD_COL_LOAD_B1") (pintype "bidirectional"))
    )
    (net (code "115") (name "Net-(SENSORB-CMD_COL_PC)") (class "Default")
      (node (ref "C26") (pin "2") (pinfunction "2_2") (pintype "passive"))
      (node (ref "SENSOR") (pin "D1") (pinfunction "CMD_COL_PC_D1") (pintype "bidirectional"))
    )
    (net (code "116") (name "Net-(SENSORB-CMD_LVDS)") (class "Default")
      (node (ref "C62") (pin "1") (pinfunction "1_1") (pintype "passive"))
      (node (ref "SENSOR") (pin "C1") (pinfunction "CMD_LVDS_C1") (pintype "bidirectional"))
    )
    (net (code "117") (name "Net-(SENSORB-CMD_RAMP)") (class "Default")
      (node (ref "C24") (pin "2") (pinfunction "2_2") (pintype "passive"))
      (node (ref "SENSOR") (pin "B29") (pinfunction "CMD_RAMP_B29") (pintype "bidirectional"))
    )
    (net (code "118") (name "Net-(SENSORB-VBGAP)") (class "Default")
      (node (ref "C64") (pin "1") (pinfunction "1_1") (pintype "passive"))
      (node (ref "SENSOR") (pin "C29") (pinfunction "VBGAP_C29") (pintype "bidirectional"))
    )
    (net (code "119") (name "Net-(SENSORB-VCLAMP)") (class "Default")
      (node (ref "C63") (pin "1") (pinfunction "1_1") (pintype "passive"))
      (node (ref "SENSOR") (pin "D4") (pinfunction "VCLAMP_D4") (pintype "bidirectional"))
    )
    (net (code "120") (name "Net-(SENSORB-VCLAMP_ADC)") (class "Default")
      (node (ref "C60") (pin "1") (pinfunction "1_1") (pintype "passive"))
      (node (ref "SENSOR") (pin "G2") (pinfunction "VCLAMP_ADC_G2") (pintype "bidirectional"))
    )
    (net (code "121") (name "Net-(SENSORB-VPCH_H)") (class "Default")
      (node (ref "C71") (pin "1") (pinfunction "1_1") (pintype "passive"))
      (node (ref "SENSOR") (pin "C4") (pinfunction "VPCH_H_C4") (pintype "bidirectional"))
    )
    (net (code "122") (name "Net-(SENSORB-VPCH_L)") (class "Default")
      (node (ref "C14") (pin "1") (pinfunction "1_1") (pintype "passive"))
      (node (ref "SENSOR") (pin "A4") (pinfunction "VPCH_L_A4") (pintype "bidirectional"))
    )
    (net (code "123") (name "Net-(SENSORB-VREF)") (class "Default")
      (node (ref "C29") (pin "1") (pinfunction "1_1") (pintype "passive"))
      (node (ref "SENSOR") (pin "A3") (pinfunction "VREF_A3") (pintype "bidirectional"))
    )
    (net (code "124") (name "Net-(SENSORB-VREF_ADC)") (class "Default")
      (node (ref "C30") (pin "1") (pinfunction "1_1") (pintype "passive"))
      (node (ref "SENSOR") (pin "B3") (pinfunction "VREF_ADC_B3") (pintype "bidirectional"))
    )
    (net (code "125") (name "Net-(SENSORB-VRES_L)") (class "Default")
      (node (ref "C15") (pin "1") (pinfunction "1_1") (pintype "passive"))
      (node (ref "SENSOR") (pin "D5") (pinfunction "VRES_L_D5") (pintype "bidirectional"))
    )
    (net (code "126") (name "Net-(SENSORB-VTF_LOW0)") (class "Default")
      (node (ref "C18") (pin "1") (pinfunction "1_1") (pintype "passive"))
      (node (ref "SENSOR") (pin "C5") (pinfunction "VTF_LOW0_C5") (pintype "bidirectional"))
    )
    (net (code "127") (name "Net-(SENSORB-VTF_LOW1)") (class "Default")
      (node (ref "C19") (pin "1") (pinfunction "1_1") (pintype "passive"))
      (node (ref "SENSOR") (pin "D6") (pinfunction "VTF_LOW1_D6") (pintype "bidirectional"))
    )
    (net (code "128") (name "Net-(SENSORB-VTF_LOW2)") (class "Default")
      (node (ref "C20") (pin "1") (pinfunction "1_1") (pintype "passive"))
      (node (ref "SENSOR") (pin "B30") (pinfunction "VTF_LOW2_B30") (pintype "bidirectional"))
    )
    (net (code "129") (name "Net-(SENSORB-VTF_LOW3)") (class "Default")
      (node (ref "C21") (pin "1") (pinfunction "1_1") (pintype "passive"))
      (node (ref "SENSOR") (pin "C30") (pinfunction "VTF_LOW3_C30") (pintype "bidirectional"))
    )
    (net (code "130") (name "Net-(U3-ADJ)") (class "Default")
      (node (ref "R21") (pin "1") (pinfunction "1_1") (pintype "passive"))
      (node (ref "R22") (pin "2") (pinfunction "2_2") (pintype "passive"))
      (node (ref "U3") (pin "5") (pinfunction "ADJ_5") (pintype "input"))
    )
    (net (code "131") (name "Net-(U6-B4)") (class "Default")
      (node (ref "TP9") (pin "TP") (pinfunction "TP_TP") (pintype "input"))
      (node (ref "U6") (pin "9") (pinfunction "B4_9") (pintype "bidirectional"))
    )
    (net (code "132") (name "Net-(UEP-WP)") (class "Default")
      (node (ref "R1X") (pin "2") (pinfunction "2_2") (pintype "passive"))
      (node (ref "R2X") (pin "1") (pinfunction "1_1") (pintype "passive"))
      (node (ref "UEP") (pin "7") (pinfunction "WP_7") (pintype "input"))
    )
    (net (code "133") (name "Net-(UNE-VINA+)") (class "Default")
      (node (ref "R7") (pin "2") (pinfunction "2_2") (pintype "passive"))
      (node (ref "R8") (pin "1") (pinfunction "1_1") (pintype "passive"))
      (node (ref "UNE") (pin "3") (pinfunction "VINA+_3") (pintype "input"))
    )
    (net (code "134") (name "Net-(UNE-VINB-)") (class "Default")
      (node (ref "R8") (pin "2") (pinfunction "2_2") (pintype "passive"))
      (node (ref "R9") (pin "1") (pinfunction "1_1") (pintype "passive"))
      (node (ref "UNE") (pin "6") (pinfunction "VINB-_6") (pintype "input"))
    )
    (net (code "135") (name "Net-(UNN-VINA+)") (class "Default")
      (node (ref "R4") (pin "2") (pinfunction "2_2") (pintype "passive"))
      (node (ref "R5") (pin "1") (pinfunction "1_1") (pintype "passive"))
      (node (ref "UNN") (pin "3") (pinfunction "VINA+_3") (pintype "input"))
    )
    (net (code "136") (name "Net-(UNN-VINB-)") (class "Default")
      (node (ref "R5") (pin "2") (pinfunction "2_2") (pintype "passive"))
      (node (ref "R6") (pin "1") (pinfunction "1_1") (pintype "passive"))
      (node (ref "UNN") (pin "6") (pinfunction "VINB-_6") (pintype "input"))
    )
    (net (code "137") (name "Net-(UNW-VINA+)") (class "Default")
      (node (ref "R1") (pin "2") (pinfunction "2_2") (pintype "passive"))
      (node (ref "R2") (pin "1") (pinfunction "1_1") (pintype "passive"))
      (node (ref "UNW") (pin "3") (pinfunction "VINA+_3") (pintype "input"))
    )
    (net (code "138") (name "Net-(UNW-VINB-)") (class "Default")
      (node (ref "R2") (pin "2") (pinfunction "2_2") (pintype "passive"))
      (node (ref "R3") (pin "1") (pinfunction "1_1") (pintype "passive"))
      (node (ref "UNW") (pin "6") (pinfunction "VINB-_6") (pintype "input"))
    )
    (net (code "139") (name "Net-(USE-VINA+)") (class "Default")
      (node (ref "R10") (pin "2") (pinfunction "2_2") (pintype "passive"))
      (node (ref "R11") (pin "1") (pinfunction "1_1") (pintype "passive"))
      (node (ref "USE") (pin "3") (pinfunction "VINA+_3") (pintype "input"))
    )
    (net (code "140") (name "Net-(USE-VINB-)") (class "Default")
      (node (ref "R11") (pin "2") (pinfunction "2_2") (pintype "passive"))
      (node (ref "R12") (pin "1") (pinfunction "1_1") (pintype "passive"))
      (node (ref "USE") (pin "6") (pinfunction "VINB-_6") (pintype "input"))
    )
    (net (code "141") (name "Net-(USS-VINA+)") (class "Default")
      (node (ref "R13") (pin "2") (pinfunction "2_2") (pintype "passive"))
      (node (ref "R14") (pin "1") (pinfunction "1_1") (pintype "passive"))
      (node (ref "USS") (pin "3") (pinfunction "VINA+_3") (pintype "input"))
    )
    (net (code "142") (name "Net-(USS-VINB-)") (class "Default")
      (node (ref "R14") (pin "2") (pinfunction "2_2") (pintype "passive"))
      (node (ref "R15") (pin "1") (pinfunction "1_1") (pintype "passive"))
      (node (ref "USS") (pin "6") (pinfunction "VINB-_6") (pintype "input"))
    )
    (net (code "143") (name "Net-(USW-VINA+)") (class "Default")
      (node (ref "R16") (pin "2") (pinfunction "2_2") (pintype "passive"))
      (node (ref "R17") (pin "1") (pinfunction "1_1") (pintype "passive"))
      (node (ref "USW") (pin "3") (pinfunction "VINA+_3") (pintype "input"))
    )
    (net (code "144") (name "Net-(USW-VINB-)") (class "Default")
      (node (ref "R17") (pin "2") (pinfunction "2_2") (pintype "passive"))
      (node (ref "R18") (pin "1") (pinfunction "1_1") (pintype "passive"))
      (node (ref "USW") (pin "6") (pinfunction "VINB-_6") (pintype "input"))
    )
    (net (code "145") (name "S00_N") (class "Default")
      (node (ref "X-SOUTH") (pin "16") (pinfunction "16_16") (pintype "bidirectional"))
    )
    (net (code "146") (name "S00_P") (class "Default")
      (node (ref "X-SOUTH") (pin "14") (pinfunction "14_14") (pintype "bidirectional"))
    )
    (net (code "147") (name "S01_N") (class "Default")
      (node (ref "X-SOUTH") (pin "17") (pinfunction "17_17") (pintype "bidirectional"))
    )
    (net (code "148") (name "S01_P") (class "Default")
      (node (ref "X-SOUTH") (pin "15") (pinfunction "15_15") (pintype "bidirectional"))
    )
    (net (code "149") (name "S02_N") (class "Default")
      (node (ref "X-SOUTH") (pin "22") (pinfunction "22_22") (pintype "bidirectional"))
    )
    (net (code "150") (name "S02_P") (class "Default")
      (node (ref "X-SOUTH") (pin "20") (pinfunction "20_20") (pintype "bidirectional"))
    )
    (net (code "151") (name "S03_N") (class "Default")
      (node (ref "X-SOUTH") (pin "23") (pinfunction "23_23") (pintype "bidirectional"))
    )
    (net (code "152") (name "S03_P") (class "Default")
      (node (ref "X-SOUTH") (pin "21") (pinfunction "21_21") (pintype "bidirectional"))
    )
    (net (code "153") (name "S04_N") (class "Default")
      (node (ref "SENSOR") (pin "C24") (pinfunction "OUT32_N_C24") (pintype "output"))
      (node (ref "X-SOUTH") (pin "28") (pinfunction "28_28") (pintype "bidirectional"))
    )
    (net (code "154") (name "S04_P") (class "Default")
      (node (ref "SENSOR") (pin "C25") (pinfunction "OUT32_P_C25") (pintype "output"))
      (node (ref "X-SOUTH") (pin "26") (pinfunction "26_26") (pintype "bidirectional"))
    )
    (net (code "155") (name "S05_N") (class "Default")
      (node (ref "X-SOUTH") (pin "29") (pinfunction "29_29") (pintype "bidirectional"))
    )
    (net (code "156") (name "S05_P") (class "Default")
      (node (ref "X-SOUTH") (pin "27") (pinfunction "27_27") (pintype "bidirectional"))
    )
    (net (code "157") (name "S06_N") (class "Default")
      (node (ref "SENSOR") (pin "D23") (pinfunction "OUT30_N_D23") (pintype "output"))
      (node (ref "X-SOUTH") (pin "34") (pinfunction "34_34") (pintype "bidirectional"))
    )
    (net (code "158") (name "S06_P") (class "Default")
      (node (ref "SENSOR") (pin "D24") (pinfunction "OUT30_P_D24") (pintype "output"))
      (node (ref "X-SOUTH") (pin "32") (pinfunction "32_32") (pintype "bidirectional"))
    )
    (net (code "159") (name "S07_N") (class "Default")
      (node (ref "SENSOR") (pin "B24") (pinfunction "OUT31_N_B24") (pintype "output"))
      (node (ref "X-SOUTH") (pin "35") (pinfunction "35_35") (pintype "bidirectional"))
    )
    (net (code "160") (name "S07_P") (class "Default")
      (node (ref "SENSOR") (pin "B25") (pinfunction "OUT31_P_B25") (pintype "output"))
      (node (ref "X-SOUTH") (pin "33") (pinfunction "33_33") (pintype "bidirectional"))
    )
    (net (code "161") (name "S08_N") (class "Default")
      (node (ref "SENSOR") (pin "D21") (pinfunction "OUT27_N_D21") (pintype "output"))
      (node (ref "X-SOUTH") (pin "40") (pinfunction "40_40") (pintype "bidirectional"))
    )
    (net (code "162") (name "S08_P") (class "Default")
      (node (ref "SENSOR") (pin "D22") (pinfunction "OUT27_P_D22") (pintype "output"))
      (node (ref "X-SOUTH") (pin "38") (pinfunction "38_38") (pintype "bidirectional"))
    )
    (net (code "163") (name "S09_N") (class "Default")
      (node (ref "SENSOR") (pin "A23") (pinfunction "OUT29_N_A23") (pintype "output"))
      (node (ref "X-SOUTH") (pin "41") (pinfunction "41_41") (pintype "bidirectional"))
    )
    (net (code "164") (name "S09_P") (class "Default")
      (node (ref "SENSOR") (pin "A24") (pinfunction "OUT29_P_A24") (pintype "output"))
      (node (ref "X-SOUTH") (pin "39") (pinfunction "39_39") (pintype "bidirectional"))
    )
    (net (code "165") (name "S10_N") (class "Default")
      (node (ref "SENSOR") (pin "C21") (pinfunction "OUT28_N_C21") (pintype "output"))
      (node (ref "X-SOUTH") (pin "46") (pinfunction "46_46") (pintype "bidirectional"))
    )
    (net (code "166") (name "S10_P") (class "Default")
      (node (ref "SENSOR") (pin "C22") (pinfunction "OUT28_P_C22") (pintype "output"))
      (node (ref "X-SOUTH") (pin "44") (pinfunction "44_44") (pintype "bidirectional"))
    )
    (net (code "167") (name "S11_N") (class "Default")
      (node (ref "SENSOR") (pin "B20") (pinfunction "OUT26_N_B20") (pintype "output"))
      (node (ref "X-SOUTH") (pin "47") (pinfunction "47_47") (pintype "bidirectional"))
    )
    (net (code "168") (name "S11_P") (class "Default")
      (node (ref "SENSOR") (pin "B21") (pinfunction "OUT26_P_B21") (pintype "output"))
      (node (ref "X-SOUTH") (pin "45") (pinfunction "45_45") (pintype "bidirectional"))
    )
    (net (code "169") (name "S12_N") (class "Default")
      (node (ref "SENSOR") (pin "D19") (pinfunction "OUT24_N_D19") (pintype "output"))
      (node (ref "X-SOUTH") (pin "52") (pinfunction "52_52") (pintype "bidirectional"))
    )
    (net (code "170") (name "S12_P") (class "Default")
      (node (ref "SENSOR") (pin "D20") (pinfunction "OUT24_P_D20") (pintype "output"))
      (node (ref "X-SOUTH") (pin "50") (pinfunction "50_50") (pintype "bidirectional"))
    )
    (net (code "171") (name "S13_N") (class "Default")
      (node (ref "SENSOR") (pin "A19") (pinfunction "OUT23_N_A19") (pintype "output"))
      (node (ref "X-SOUTH") (pin "53") (pinfunction "53_53") (pintype "bidirectional"))
    )
    (net (code "172") (name "S13_P") (class "Default")
      (node (ref "SENSOR") (pin "A20") (pinfunction "OUT23_P_A20") (pintype "output"))
      (node (ref "X-SOUTH") (pin "51") (pinfunction "51_51") (pintype "bidirectional"))
    )
    (net (code "173") (name "S14_N") (class "Default")
      (node (ref "SENSOR") (pin "C19") (pinfunction "OUT25_N_C19") (pintype "output"))
      (node (ref "X-SOUTH") (pin "58") (pinfunction "58_58") (pintype "bidirectional"))
    )
    (net (code "174") (name "S14_P") (class "Default")
      (node (ref "SENSOR") (pin "C20") (pinfunction "OUT25_P_C20") (pintype "output"))
      (node (ref "X-SOUTH") (pin "56") (pinfunction "56_56") (pintype "bidirectional"))
    )
    (net (code "175") (name "S15_N") (class "Default")
      (node (ref "SENSOR") (pin "B18") (pinfunction "OUT22_N_B18") (pintype "output"))
      (node (ref "X-SOUTH") (pin "59") (pinfunction "59_59") (pintype "bidirectional"))
    )
    (net (code "176") (name "S15_P") (class "Default")
      (node (ref "SENSOR") (pin "B19") (pinfunction "OUT22_P_B19") (pintype "output"))
      (node (ref "X-SOUTH") (pin "57") (pinfunction "57_57") (pintype "bidirectional"))
    )
    (net (code "177") (name "S16_N") (class "Default")
      (node (ref "SENSOR") (pin "C17") (pinfunction "OUT21_N_C17") (pintype "output"))
      (node (ref "X-SOUTH") (pin "64") (pinfunction "64_64") (pintype "bidirectional"))
    )
    (net (code "178") (name "S16_P") (class "Default")
      (node (ref "SENSOR") (pin "C18") (pinfunction "OUT21_P_C18") (pintype "output"))
      (node (ref "X-SOUTH") (pin "62") (pinfunction "62_62") (pintype "bidirectional"))
    )
    (net (code "179") (name "S17_N") (class "Default")
      (node (ref "SENSOR") (pin "A17") (pinfunction "OUT19_N_A17") (pintype "output"))
      (node (ref "X-SOUTH") (pin "65") (pinfunction "65_65") (pintype "bidirectional"))
    )
    (net (code "180") (name "S17_P") (class "Default")
      (node (ref "SENSOR") (pin "A18") (pinfunction "OUT19_P_A18") (pintype "output"))
      (node (ref "X-SOUTH") (pin "63") (pinfunction "63_63") (pintype "bidirectional"))
    )
    (net (code "181") (name "S18_N") (class "Default")
      (node (ref "SENSOR") (pin "D17") (pinfunction "OUT20_N_D17") (pintype "output"))
      (node (ref "X-SOUTH") (pin "70") (pinfunction "70_70") (pintype "bidirectional"))
    )
    (net (code "182") (name "S18_P") (class "Default")
      (node (ref "SENSOR") (pin "D18") (pinfunction "OUT20_P_D18") (pintype "output"))
      (node (ref "X-SOUTH") (pin "68") (pinfunction "68_68") (pintype "bidirectional"))
    )
    (net (code "183") (name "S19_N") (class "Default")
      (node (ref "SENSOR") (pin "B16") (pinfunction "OUT18_N_B16") (pintype "output"))
      (node (ref "X-SOUTH") (pin "71") (pinfunction "71_71") (pintype "bidirectional"))
    )
    (net (code "184") (name "S19_P") (class "Default")
      (node (ref "SENSOR") (pin "B17") (pinfunction "OUT18_P_B17") (pintype "output"))
      (node (ref "X-SOUTH") (pin "69") (pinfunction "69_69") (pintype "bidirectional"))
    )
    (net (code "185") (name "S20_N") (class "Default")
      (node (ref "SENSOR") (pin "D15") (pinfunction "OUT17_N_D15") (pintype "output"))
      (node (ref "X-SOUTH") (pin "76") (pinfunction "76_76") (pintype "bidirectional"))
    )
    (net (code "186") (name "S20_P") (class "Default")
      (node (ref "SENSOR") (pin "D16") (pinfunction "OUT17_P_D16") (pintype "output"))
      (node (ref "X-SOUTH") (pin "74") (pinfunction "74_74") (pintype "bidirectional"))
    )
    (net (code "187") (name "S21_N") (class "Default")
      (node (ref "SENSOR") (pin "B14") (pinfunction "OUT16_N_B14") (pintype "output"))
      (node (ref "X-SOUTH") (pin "77") (pinfunction "77_77") (pintype "bidirectional"))
    )
    (net (code "188") (name "S21_P") (class "Default")
      (node (ref "SENSOR") (pin "B15") (pinfunction "OUT16_P_B15") (pintype "output"))
      (node (ref "X-SOUTH") (pin "75") (pinfunction "75_75") (pintype "bidirectional"))
    )
    (net (code "189") (name "S22_N") (class "Default")
      (node (ref "SENSOR") (pin "D13") (pinfunction "OUT15_N_D13") (pintype "output"))
      (node (ref "X-SOUTH") (pin "82") (pinfunction "82_82") (pintype "bidirectional"))
    )
    (net (code "190") (name "S22_P") (class "Default")
      (node (ref "SENSOR") (pin "D14") (pinfunction "OUT15_P_D14") (pintype "output"))
      (node (ref "X-SOUTH") (pin "80") (pinfunction "80_80") (pintype "bidirectional"))
    )
    (net (code "191") (name "S23_N") (class "Default")
      (node (ref "SENSOR") (pin "A13") (pinfunction "OUT13_N_A13") (pintype "output"))
      (node (ref "X-SOUTH") (pin "83") (pinfunction "83_83") (pintype "bidirectional"))
    )
    (net (code "192") (name "S23_P") (class "Default")
      (node (ref "SENSOR") (pin "A14") (pinfunction "OUT13_P_A14") (pintype "output"))
      (node (ref "X-SOUTH") (pin "81") (pinfunction "81_81") (pintype "bidirectional"))
    )
    (net (code "193") (name "S24_N") (class "Default")
      (node (ref "SENSOR") (pin "C13") (pinfunction "OUT14_N_C13") (pintype "output"))
      (node (ref "X-SOUTH") (pin "88") (pinfunction "88_88") (pintype "bidirectional"))
    )
    (net (code "194") (name "S24_P") (class "Default")
      (node (ref "SENSOR") (pin "C14") (pinfunction "OUT14_P_C14") (pintype "output"))
      (node (ref "X-SOUTH") (pin "86") (pinfunction "86_86") (pintype "bidirectional"))
    )
    (net (code "195") (name "S25_N") (class "Default")
      (node (ref "SENSOR") (pin "B12") (pinfunction "OUT12_N_B12") (pintype "output"))
      (node (ref "X-SOUTH") (pin "89") (pinfunction "89_89") (pintype "bidirectional"))
    )
    (net (code "196") (name "S25_P") (class "Default")
      (node (ref "SENSOR") (pin "B13") (pinfunction "OUT12_P_B13") (pintype "output"))
      (node (ref "X-SOUTH") (pin "87") (pinfunction "87_87") (pintype "bidirectional"))
    )
    (net (code "197") (name "S26_N") (class "Default")
      (node (ref "SENSOR") (pin "D11") (pinfunction "OUT10_N_D11") (pintype "output"))
      (node (ref "X-SOUTH") (pin "94") (pinfunction "94_94") (pintype "bidirectional"))
    )
    (net (code "198") (name "S26_P") (class "Default")
      (node (ref "SENSOR") (pin "D12") (pinfunction "OUT10_P_D12") (pintype "output"))
      (node (ref "X-SOUTH") (pin "92") (pinfunction "92_92") (pintype "bidirectional"))
    )
    (net (code "199") (name "S27_N") (class "Default")
      (node (ref "SENSOR") (pin "A11") (pinfunction "OUT9_N_A11") (pintype "output"))
      (node (ref "X-SOUTH") (pin "95") (pinfunction "95_95") (pintype "bidirectional"))
    )
    (net (code "200") (name "S27_P") (class "Default")
      (node (ref "SENSOR") (pin "A12") (pinfunction "OUT9_P_A12") (pintype "output"))
      (node (ref "X-SOUTH") (pin "93") (pinfunction "93_93") (pintype "bidirectional"))
    )
    (net (code "201") (name "S28_N") (class "Default")
      (node (ref "SENSOR") (pin "C11") (pinfunction "OUT11_N_C11") (pintype "output"))
      (node (ref "X-SOUTH") (pin "100") (pinfunction "100_100") (pintype "bidirectional"))
    )
    (net (code "202") (name "S28_P") (class "Default")
      (node (ref "SENSOR") (pin "C12") (pinfunction "OUT11_P_C12") (pintype "output"))
      (node (ref "X-SOUTH") (pin "98") (pinfunction "98_98") (pintype "bidirectional"))
    )
    (net (code "203") (name "S29_N") (class "Default")
      (node (ref "SENSOR") (pin "B10") (pinfunction "OUT8_N_B10") (pintype "output"))
      (node (ref "X-SOUTH") (pin "101") (pinfunction "101_101") (pintype "bidirectional"))
    )
    (net (code "204") (name "S29_P") (class "Default")
      (node (ref "SENSOR") (pin "B11") (pinfunction "OUT8_P_B11") (pintype "output"))
      (node (ref "X-SOUTH") (pin "99") (pinfunction "99_99") (pintype "bidirectional"))
    )
    (net (code "205") (name "S30_N") (class "Default")
      (node (ref "SENSOR") (pin "C9") (pinfunction "OUT7_N_C9") (pintype "output"))
      (node (ref "X-SOUTH") (pin "106") (pinfunction "106_106") (pintype "bidirectional"))
    )
    (net (code "206") (name "S30_P") (class "Default")
      (node (ref "SENSOR") (pin "C10") (pinfunction "OUT7_P_C10") (pintype "output"))
      (node (ref "X-SOUTH") (pin "104") (pinfunction "104_104") (pintype "bidirectional"))
    )
    (net (code "207") (name "S31_N") (class "Default")
      (node (ref "SENSOR") (pin "B8") (pinfunction "OUT5_N_B8") (pintype "output"))
      (node (ref "X-SOUTH") (pin "107") (pinfunction "107_107") (pintype "bidirectional"))
    )
    (net (code "208") (name "S31_P") (class "Default")
      (node (ref "SENSOR") (pin "B9") (pinfunction "OUT5_P_B9") (pintype "output"))
      (node (ref "X-SOUTH") (pin "105") (pinfunction "105_105") (pintype "bidirectional"))
    )
    (net (code "209") (name "S32_N") (class "Default")
      (node (ref "SENSOR") (pin "D9") (pinfunction "OUT6_N_D9") (pintype "output"))
      (node (ref "X-SOUTH") (pin "112") (pinfunction "112_112") (pintype "bidirectional"))
    )
    (net (code "210") (name "S32_P") (class "Default")
      (node (ref "SENSOR") (pin "D10") (pinfunction "OUT6_P_D10") (pintype "output"))
      (node (ref "X-SOUTH") (pin "110") (pinfunction "110_110") (pintype "bidirectional"))
    )
    (net (code "211") (name "S33_N") (class "Default")
      (node (ref "SENSOR") (pin "A7") (pinfunction "OUT2_N_A7") (pintype "output"))
      (node (ref "X-SOUTH") (pin "113") (pinfunction "113_113") (pintype "bidirectional"))
    )
    (net (code "212") (name "S33_P") (class "Default")
      (node (ref "SENSOR") (pin "A8") (pinfunction "OUT2_P_A8") (pintype "output"))
      (node (ref "X-SOUTH") (pin "111") (pinfunction "111_111") (pintype "bidirectional"))
    )
    (net (code "213") (name "S34_N") (class "Default")
      (node (ref "SENSOR") (pin "C7") (pinfunction "OUT4_N_C7") (pintype "output"))
      (node (ref "X-SOUTH") (pin "118") (pinfunction "118_118") (pintype "bidirectional"))
    )
    (net (code "214") (name "S34_P") (class "Default")
      (node (ref "SENSOR") (pin "C8") (pinfunction "OUT4_P_C8") (pintype "output"))
      (node (ref "X-SOUTH") (pin "116") (pinfunction "116_116") (pintype "bidirectional"))
    )
    (net (code "215") (name "S35_N") (class "Default")
      (node (ref "SENSOR") (pin "B6") (pinfunction "OUT1_N_B6") (pintype "output"))
      (node (ref "X-SOUTH") (pin "119") (pinfunction "119_119") (pintype "bidirectional"))
    )
    (net (code "216") (name "S35_P") (class "Default")
      (node (ref "SENSOR") (pin "B7") (pinfunction "OUT1_P_B7") (pintype "output"))
      (node (ref "X-SOUTH") (pin "117") (pinfunction "117_117") (pintype "bidirectional"))
    )
    (net (code "217") (name "S36_N") (class "Default")
      (node (ref "SENSOR") (pin "D7") (pinfunction "OUT3_N_D7") (pintype "output"))
      (node (ref "X-SOUTH") (pin "124") (pinfunction "124_124") (pintype "bidirectional"))
    )
    (net (code "218") (name "S36_P") (class "Default")
      (node (ref "SENSOR") (pin "D8") (pinfunction "OUT3_P_D8") (pintype "output"))
      (node (ref "X-SOUTH") (pin "122") (pinfunction "122_122") (pintype "bidirectional"))
    )
    (net (code "219") (name "S37_N") (class "Default")
      (node (ref "SENSOR") (pin "A5") (pinfunction "OUTCTR_N_A5") (pintype "output"))
      (node (ref "X-SOUTH") (pin "125") (pinfunction "125_125") (pintype "bidirectional"))
    )
    (net (code "220") (name "S37_P") (class "Default")
      (node (ref "SENSOR") (pin "A6") (pinfunction "OUTCTR_P_A6") (pintype "output"))
      (node (ref "X-SOUTH") (pin "123") (pinfunction "123_123") (pintype "bidirectional"))
    )
    (net (code "221") (name "S38_N") (class "Default")
      (node (ref "X-SOUTH") (pin "130") (pinfunction "130_130") (pintype "bidirectional"))
    )
    (net (code "222") (name "S38_P") (class "Default")
      (node (ref "X-SOUTH") (pin "128") (pinfunction "128_128") (pintype "bidirectional"))
    )
    (net (code "223") (name "S39_N") (class "Default")
      (node (ref "U3") (pin "6") (pinfunction "EN_6") (pintype "input"))
      (node (ref "X-SOUTH") (pin "131") (pinfunction "131_131") (pintype "bidirectional"))
    )
    (net (code "224") (name "S39_P") (class "Default")
      (node (ref "X-SOUTH") (pin "129") (pinfunction "129_129") (pintype "bidirectional"))
    )
    (net (code "225") (name "SPI_CLK") (class "Default")
      (node (ref "SENSOR") (pin "H29") (pinfunction "SPI_CLK_H29") (pintype "input"))
      (node (ref "U4") (pin "9") (pinfunction "B4_9") (pintype "bidirectional"))
    )
    (net (code "226") (name "SPI_EN") (class "Default")
      (node (ref "SENSOR") (pin "F28") (pinfunction "SPI_EN_F28") (pintype "input"))
      (node (ref "U4") (pin "12") (pinfunction "B1_12") (pintype "bidirectional"))
    )
    (net (code "227") (name "SPI_IN") (class "Default")
      (node (ref "SENSOR") (pin "E28") (pinfunction "SPI_IN_E28") (pintype "input"))
      (node (ref "U4") (pin "10") (pinfunction "B3_10") (pintype "bidirectional"))
    )
    (net (code "228") (name "SPI_OUT") (class "Default")
      (node (ref "SENSOR") (pin "G28") (pinfunction "SPI_OUT_G28") (pintype "output"))
      (node (ref "U4") (pin "11") (pinfunction "B2_11") (pintype "bidirectional"))
    )
    (net (code "229") (name "SYS_RES_N") (class "Default")
      (node (ref "SENSOR") (pin "F30") (pinfunction "SYS_RES_N_F30") (pintype "input"))
      (node (ref "U5") (pin "10") (pinfunction "B3_10") (pintype "bidirectional"))
    )
    (net (code "230") (name "S_CHK_EN") (class "Default")
      (node (ref "X-SOUTH") (pin "8") (pinfunction "8_8") (pintype "bidirectional"))
    )
    (net (code "231") (name "S_CHK_V") (class "Default")
      (node (ref "C5") (pin "1") (pinfunction "1_1") (pintype "passive"))
      (node (ref "C6") (pin "1") (pinfunction "1_1") (pintype "passive"))
      (node (ref "C7") (pin "1") (pinfunction "1_1") (pintype "passive"))
      (node (ref "R20") (pin "1") (pinfunction "1_1") (pintype "passive"))
      (node (ref "TP3") (pin "TP") (pinfunction "TP_TP") (pintype "input"))
      (node (ref "USE") (pin "8") (pinfunction "VDD_8") (pintype "power_in"))
      (node (ref "USS") (pin "8") (pinfunction "VDD_8") (pintype "power_in"))
      (node (ref "USW") (pin "8") (pinfunction "VDD_8") (pintype "power_in"))
      (node (ref "X-SOUTH") (pin "10") (pinfunction "10_10") (pintype "bidirectional"))
    )
    (net (code "232") (name "S_I2C_EN") (class "Default")
      (node (ref "X-SOUTH") (pin "137") (pinfunction "137_137") (pintype "bidirectional"))
    )
    (net (code "233") (name "S_I2C_V") (class "Default")
      (node (ref "U7") (pin "8") (pinfunction "VCC_8") (pintype "power_in"))
      (node (ref "X-SOUTH") (pin "135") (pinfunction "135_135") (pintype "bidirectional"))
    )
    (net (code "234") (name "S_REF") (class "Default")
      (node (ref "R20") (pin "2") (pinfunction "2_2") (pintype "passive"))
      (node (ref "TP4") (pin "TP") (pinfunction "TP_TP") (pintype "input"))
      (node (ref "U2") (pin "1") (pinfunction "CATHODE_1") (pintype "output"))
      (node (ref "U2") (pin "3") (pinfunction "REF_3") (pintype "input"))
      (node (ref "USE") (pin "2") (pinfunction "VINA-_2") (pintype "input"))
      (node (ref "USE") (pin "5") (pinfunction "VINB+_5") (pintype "input"))
      (node (ref "USS") (pin "2") (pinfunction "VINA-_2") (pintype "input"))
      (node (ref "USS") (pin "5") (pinfunction "VINB+_5") (pintype "input"))
      (node (ref "USW") (pin "2") (pinfunction "VINA-_2") (pintype "input"))
      (node (ref "USW") (pin "5") (pinfunction "VINB+_5") (pintype "input"))
    )
    (net (code "235") (name "S_SCK") (class "Default")
      (node (ref "X-SOUTH") (pin "144") (pinfunction "144_144") (pintype "bidirectional"))
    )
    (net (code "236") (name "S_SCL") (class "Default")
      (node (ref "U7") (pin "2") (pinfunction "SCL_2") (pintype "input"))
      (node (ref "X-SOUTH") (pin "143") (pinfunction "143_143") (pintype "bidirectional"))
    )
    (net (code "237") (name "S_SDA") (class "Default")
      (node (ref "U7") (pin "1") (pinfunction "SDA_1") (pintype "bidirectional"))
      (node (ref "X-SOUTH") (pin "141") (pinfunction "141_141") (pintype "bidirectional"))
    )
    (net (code "238") (name "S_SDI") (class "Default")
      (node (ref "X-SOUTH") (pin "140") (pinfunction "140_140") (pintype "bidirectional"))
    )
    (net (code "239") (name "S_SDO") (class "Default")
      (node (ref "X-SOUTH") (pin "142") (pinfunction "142_142") (pintype "bidirectional"))
    )
    (net (code "240") (name "S_SPI_EN") (class "Default")
      (node (ref "X-SOUTH") (pin "136") (pinfunction "136_136") (pintype "bidirectional"))
    )
    (net (code "241") (name "S_SPI_V") (class "Default")
      (node (ref "X-SOUTH") (pin "134") (pinfunction "134_134") (pintype "bidirectional"))
    )
    (net (code "242") (name "S_VE") (class "Default")
      (node (ref "X-SOUTH") (pin "13") (pinfunction "13_13") (pintype "bidirectional"))
      (node (ref "X-SOUTH") (pin "19") (pinfunction "19_19") (pintype "bidirectional"))
      (node (ref "X-SOUTH") (pin "25") (pinfunction "25_25") (pintype "bidirectional"))
      (node (ref "X-SOUTH") (pin "31") (pinfunction "31_31") (pintype "bidirectional"))
      (node (ref "X-SOUTH") (pin "37") (pinfunction "37_37") (pintype "bidirectional"))
    )
    (net (code "243") (name "S_VE_CV") (class "Default")
      (node (ref "C11") (pin "1") (pinfunction "1_1") (pintype "passive"))
      (node (ref "R10") (pin "1") (pinfunction "1_1") (pintype "passive"))
      (node (ref "X-SOUTH") (pin "2") (pinfunction "2_2") (pintype "bidirectional"))
    )
    (net (code "244") (name "S_VE_OV") (class "Default")
      (node (ref "USE") (pin "7") (pinfunction "OUTB_7") (pintype "output"))
      (node (ref "X-SOUTH") (pin "1") (pinfunction "1_1") (pintype "bidirectional"))
    )
    (net (code "245") (name "S_VE_UV") (class "Default")
      (node (ref "USE") (pin "1") (pinfunction "OUTA_1") (pintype "output"))
      (node (ref "X-SOUTH") (pin "7") (pinfunction "7_7") (pintype "bidirectional"))
    )
    (net (code "246") (name "S_VS") (class "Default")
      (node (ref "C45") (pin "1") (pinfunction "1_1") (pintype "passive"))
      (node (ref "C46") (pin "1") (pinfunction "1_1") (pintype "passive"))
      (node (ref "C47") (pin "1") (pinfunction "1_1") (pintype "passive"))
      (node (ref "C48") (pin "1") (pinfunction "1_1") (pintype "passive"))
      (node (ref "C49") (pin "1") (pinfunction "1_1") (pintype "passive"))
      (node (ref "C72") (pin "1") (pinfunction "1_1") (pintype "passive"))
      (node (ref "C73") (pin "1") (pinfunction "1_1") (pintype "passive"))
      (node (ref "C74") (pin "1") (pinfunction "1_1") (pintype "passive"))
      (node (ref "C81") (pin "1") (pinfunction "1_1") (pintype "passive"))
      (node (ref "C82") (pin "1") (pinfunction "1_1") (pintype "passive"))
      (node (ref "C83") (pin "1") (pinfunction "1_1") (pintype "passive"))
      (node (ref "SENSOR") (pin "A30") (pinfunction "VDD_PIX_A30") (pintype "power_in"))
      (node (ref "SENSOR") (pin "D28") (pinfunction "VDD_PIX_D28") (pintype "power_in"))
      (node (ref "SENSOR") (pin "D30") (pinfunction "VDD_PIX_D30") (pintype "power_in"))
      (node (ref "SENSOR") (pin "G1") (pinfunction "VDD_PIX_G1") (pintype "power_in"))
      (node (ref "SENSOR") (pin "H28") (pinfunction "VDD_PIX_H28") (pintype "power_in"))
      (node (ref "TP6") (pin "TP") (pinfunction "TP_TP") (pintype "input"))
      (node (ref "X-SOUTH") (pin "49") (pinfunction "49_49") (pintype "bidirectional"))
      (node (ref "X-SOUTH") (pin "55") (pinfunction "55_55") (pintype "bidirectional"))
      (node (ref "X-SOUTH") (pin "61") (pinfunction "61_61") (pintype "bidirectional"))
      (node (ref "X-SOUTH") (pin "67") (pinfunction "67_67") (pintype "bidirectional"))
      (node (ref "X-SOUTH") (pin "73") (pinfunction "73_73") (pintype "bidirectional"))
      (node (ref "X-SOUTH") (pin "79") (pinfunction "79_79") (pintype "bidirectional"))
      (node (ref "X-SOUTH") (pin "85") (pinfunction "85_85") (pintype "bidirectional"))
      (node (ref "X-SOUTH") (pin "91") (pinfunction "91_91") (pintype "bidirectional"))
      (node (ref "X-SOUTH") (pin "97") (pinfunction "97_97") (pintype "bidirectional"))
    )
    (net (code "247") (name "S_VS_CV") (class "Default")
      (node (ref "C12") (pin "1") (pinfunction "1_1") (pintype "passive"))
      (node (ref "R13") (pin "1") (pinfunction "1_1") (pintype "passive"))
      (node (ref "X-SOUTH") (pin "4") (pinfunction "4_4") (pintype "bidirectional"))
    )
    (net (code "248") (name "S_VS_OV") (class "Default")
      (node (ref "USS") (pin "7") (pinfunction "OUTB_7") (pintype "output"))
      (node (ref "X-SOUTH") (pin "3") (pinfunction "3_3") (pintype "bidirectional"))
    )
    (net (code "249") (name "S_VS_UV") (class "Default")
      (node (ref "USS") (pin "1") (pinfunction "OUTA_1") (pintype "output"))
      (node (ref "X-SOUTH") (pin "9") (pinfunction "9_9") (pintype "bidirectional"))
    )
    (net (code "250") (name "S_VW") (class "Default")
      (node (ref "C90") (pin "1") (pinfunction "1_1") (pintype "passive"))
      (node (ref "U3") (pin "1") (pinfunction "BIAS_1") (pintype "power_in"))
      (node (ref "U3") (pin "3") (pinfunction "IN_3") (pintype "power_in"))
      (node (ref "X-SOUTH") (pin "109") (pinfunction "109_109") (pintype "bidirectional"))
      (node (ref "X-SOUTH") (pin "115") (pinfunction "115_115") (pintype "bidirectional"))
      (node (ref "X-SOUTH") (pin "121") (pinfunction "121_121") (pintype "bidirectional"))
      (node (ref "X-SOUTH") (pin "127") (pinfunction "127_127") (pintype "bidirectional"))
      (node (ref "X-SOUTH") (pin "133") (pinfunction "133_133") (pintype "bidirectional"))
    )
    (net (code "251") (name "S_VW_CV") (class "Default")
      (node (ref "C13") (pin "1") (pinfunction "1_1") (pintype "passive"))
      (node (ref "R16") (pin "1") (pinfunction "1_1") (pintype "passive"))
      (node (ref "X-SOUTH") (pin "6") (pinfunction "6_6") (pintype "bidirectional"))
    )
    (net (code "252") (name "S_VW_OV") (class "Default")
      (node (ref "USW") (pin "7") (pinfunction "OUTB_7") (pintype "output"))
      (node (ref "X-SOUTH") (pin "5") (pinfunction "5_5") (pintype "bidirectional"))
    )
    (net (code "253") (name "S_VW_UV") (class "Default")
      (node (ref "USW") (pin "1") (pinfunction "OUTA_1") (pintype "output"))
      (node (ref "X-SOUTH") (pin "11") (pinfunction "11_11") (pintype "bidirectional"))
    )
    (net (code "254") (name "TDIG1") (class "Default")
      (node (ref "SENSOR") (pin "G27") (pinfunction "TDIG1_G27") (pintype "output"))
      (node (ref "U5") (pin "9") (pinfunction "B4_9") (pintype "bidirectional"))
    )
    (net (code "255") (name "TDIG2") (class "Default")
      (node (ref "SENSOR") (pin "G26") (pinfunction "TDIG2_G26") (pintype "output"))
      (node (ref "U6") (pin "11") (pinfunction "B2_11") (pintype "bidirectional"))
    )
    (net (code "256") (name "T_EXP1") (class "Default")
      (node (ref "SENSOR") (pin "H30") (pinfunction "T_EXP1_H30") (pintype "input"))
      (node (ref "U5") (pin "12") (pinfunction "B1_12") (pintype "bidirectional"))
    )
    (net (code "257") (name "T_EXP2") (class "Default")
      (node (ref "SENSOR") (pin "E29") (pinfunction "T_EXP2_E29") (pintype "input"))
      (node (ref "U6") (pin "10") (pinfunction "B3_10") (pintype "bidirectional"))
    )
    (net (code "258") (name "VRAMP1") (class "Default")
      (node (ref "C16") (pin "1") (pinfunction "1_1") (pintype "passive"))
      (node (ref "R23") (pin "1") (pinfunction "1_1") (pintype "passive"))
      (node (ref "SENSOR") (pin "G29") (pinfunction "VRAMP1_G29") (pintype "bidirectional"))
    )
    (net (code "259") (name "VRAMP2") (class "Default")
      (node (ref "C17") (pin "1") (pinfunction "1_1") (pintype "passive"))
      (node (ref "R23") (pin "2") (pinfunction "2_2") (pintype "passive"))
      (node (ref "SENSOR") (pin "F29") (pinfunction "VRAMP2_F29") (pintype "bidirectional"))
    )
    (net (code "260") (name "VTREF") (class "Default")
      (node (ref "C65") (pin "1") (pinfunction "1_1") (pintype "passive"))
      (node (ref "C91") (pin "2") (pinfunction "2_2") (pintype "passive"))
      (node (ref "R21") (pin "2") (pinfunction "2_2") (pintype "passive"))
      (node (ref "R24") (pin "1") (pinfunction "1_1") (pintype "passive"))
      (node (ref "SENSOR") (pin "B2") (pinfunction "VTREF_B2") (pintype "bidirectional"))
      (node (ref "U3") (pin "4") (pinfunction "OUT_4") (pintype "power_in"))
    )
    (net (code "261") (name "VTSIG") (class "Default")
      (node (ref "C66") (pin "1") (pinfunction "1_1") (pintype "passive"))
      (node (ref "R24") (pin "2") (pinfunction "2_2") (pintype "passive"))
      (node (ref "SENSOR") (pin "C2") (pinfunction "VTSIG_C2") (pintype "bidirectional"))
    )
    (net (code "262") (name "unconnected-(U1-NC-Pad2)") (class "Default")
      (node (ref "U1") (pin "2") (pinfunction "NC_2") (pintype "no_connect"))
    )
    (net (code "263") (name "unconnected-(U1-NC-Pad4)") (class "Default")
      (node (ref "U1") (pin "4") (pinfunction "NC_4") (pintype "no_connect"))
    )
    (net (code "264") (name "unconnected-(U1-NC-Pad5)") (class "Default")
      (node (ref "U1") (pin "5") (pinfunction "NC_5") (pintype "no_connect"))
    )
    (net (code "265") (name "unconnected-(U2-NC-Pad2)") (class "Default")
      (node (ref "U2") (pin "2") (pinfunction "NC_2") (pintype "no_connect"))
    )
    (net (code "266") (name "unconnected-(U2-NC-Pad4)") (class "Default")
      (node (ref "U2") (pin "4") (pinfunction "NC_4") (pintype "no_connect"))
    )
    (net (code "267") (name "unconnected-(U2-NC-Pad5)") (class "Default")
      (node (ref "U2") (pin "5") (pinfunction "NC_5") (pintype "no_connect"))
    )
    (net (code "268") (name "unconnected-(U7-OS-Pad3)") (class "Default")
      (node (ref "U7") (pin "3") (pinfunction "OS_3") (pintype "output"))
    )
    (net (code "269") (name "unconnected-(X-NORTH-PadM1)") (class "Default")
      (node (ref "X-NORTH") (pin "M1") (pinfunction "M1_M1") (pintype "bidirectional"))
    )
    (net (code "270") (name "unconnected-(X-NORTH-PadM2)") (class "Default")
      (node (ref "X-NORTH") (pin "M2") (pinfunction "M2_M2") (pintype "bidirectional"))
    )
    (net (code "271") (name "unconnected-(X-SOUTH-PadM1)") (class "Default")
      (node (ref "X-SOUTH") (pin "M1") (pinfunction "M1_M1") (pintype "bidirectional"))
    )
    (net (code "272") (name "unconnected-(X-SOUTH-PadM2)") (class "Default")
      (node (ref "X-SOUTH") (pin "M2") (pinfunction "M2_M2") (pintype "bidirectional"))
    )
  )
)
